# SCH_ONO_R2.net
KiCad netlist of a schematic drawn in EasyEDA
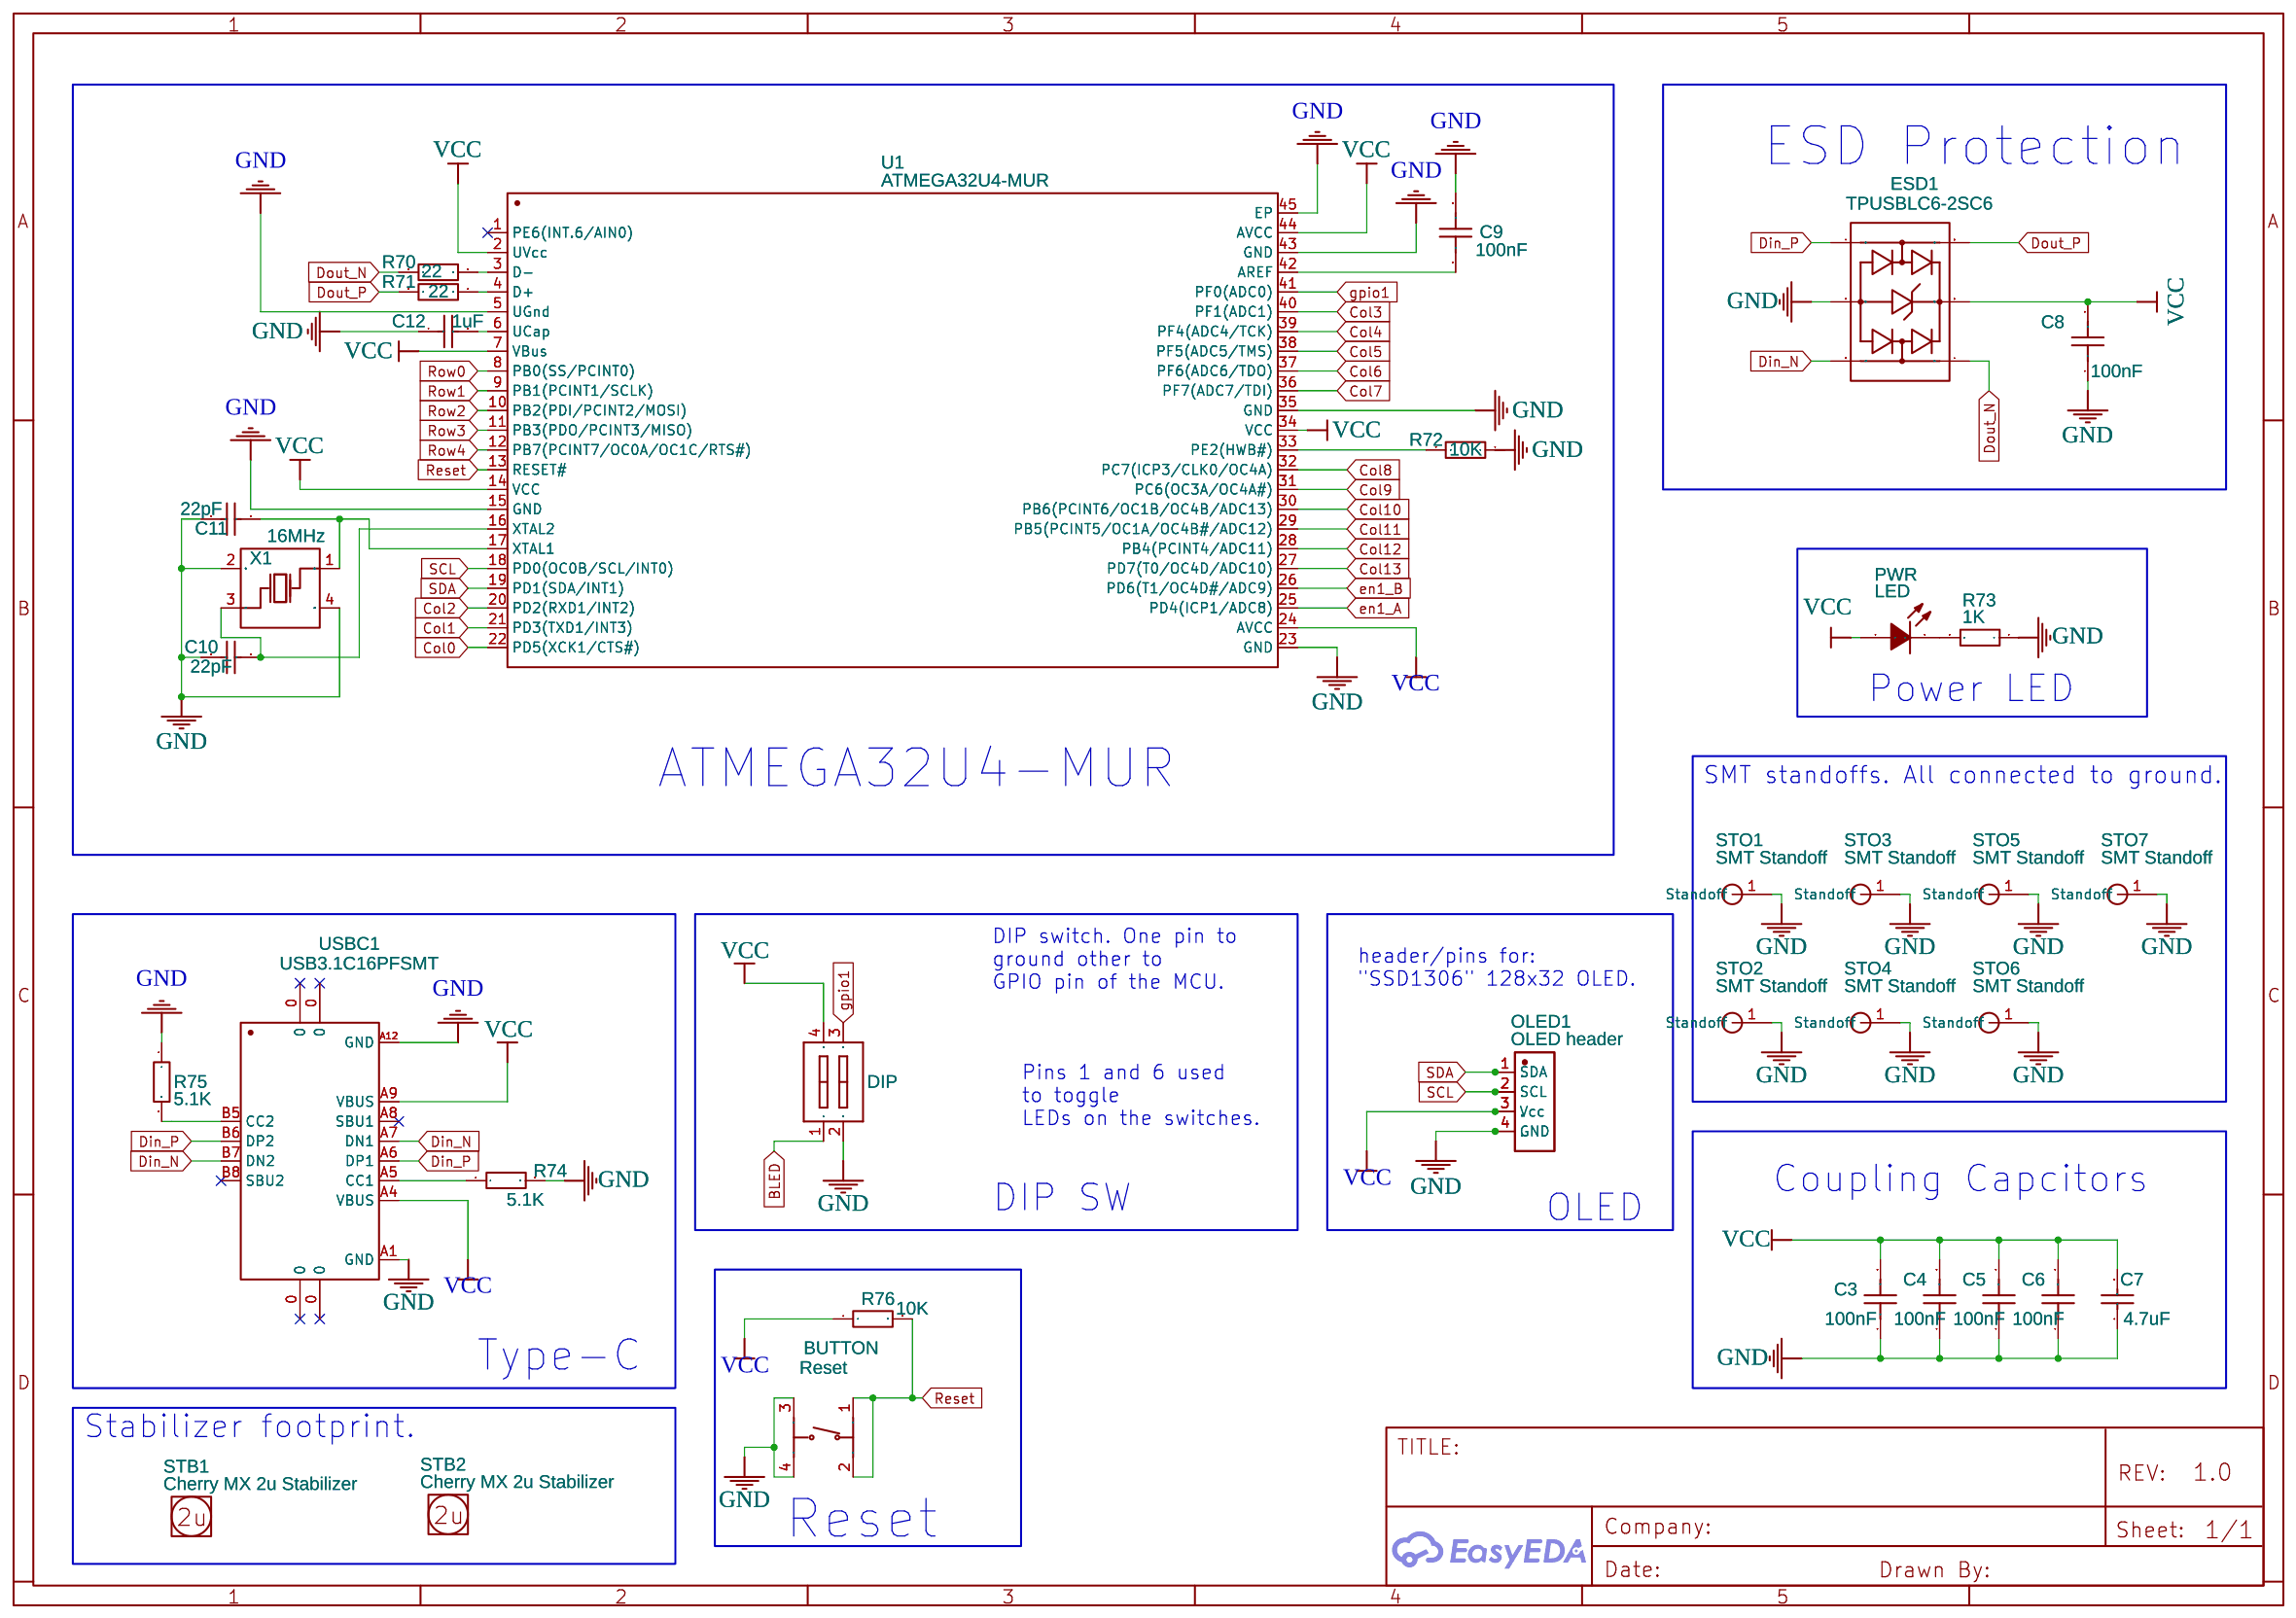
[diagram p0: Atmega MCU copy]
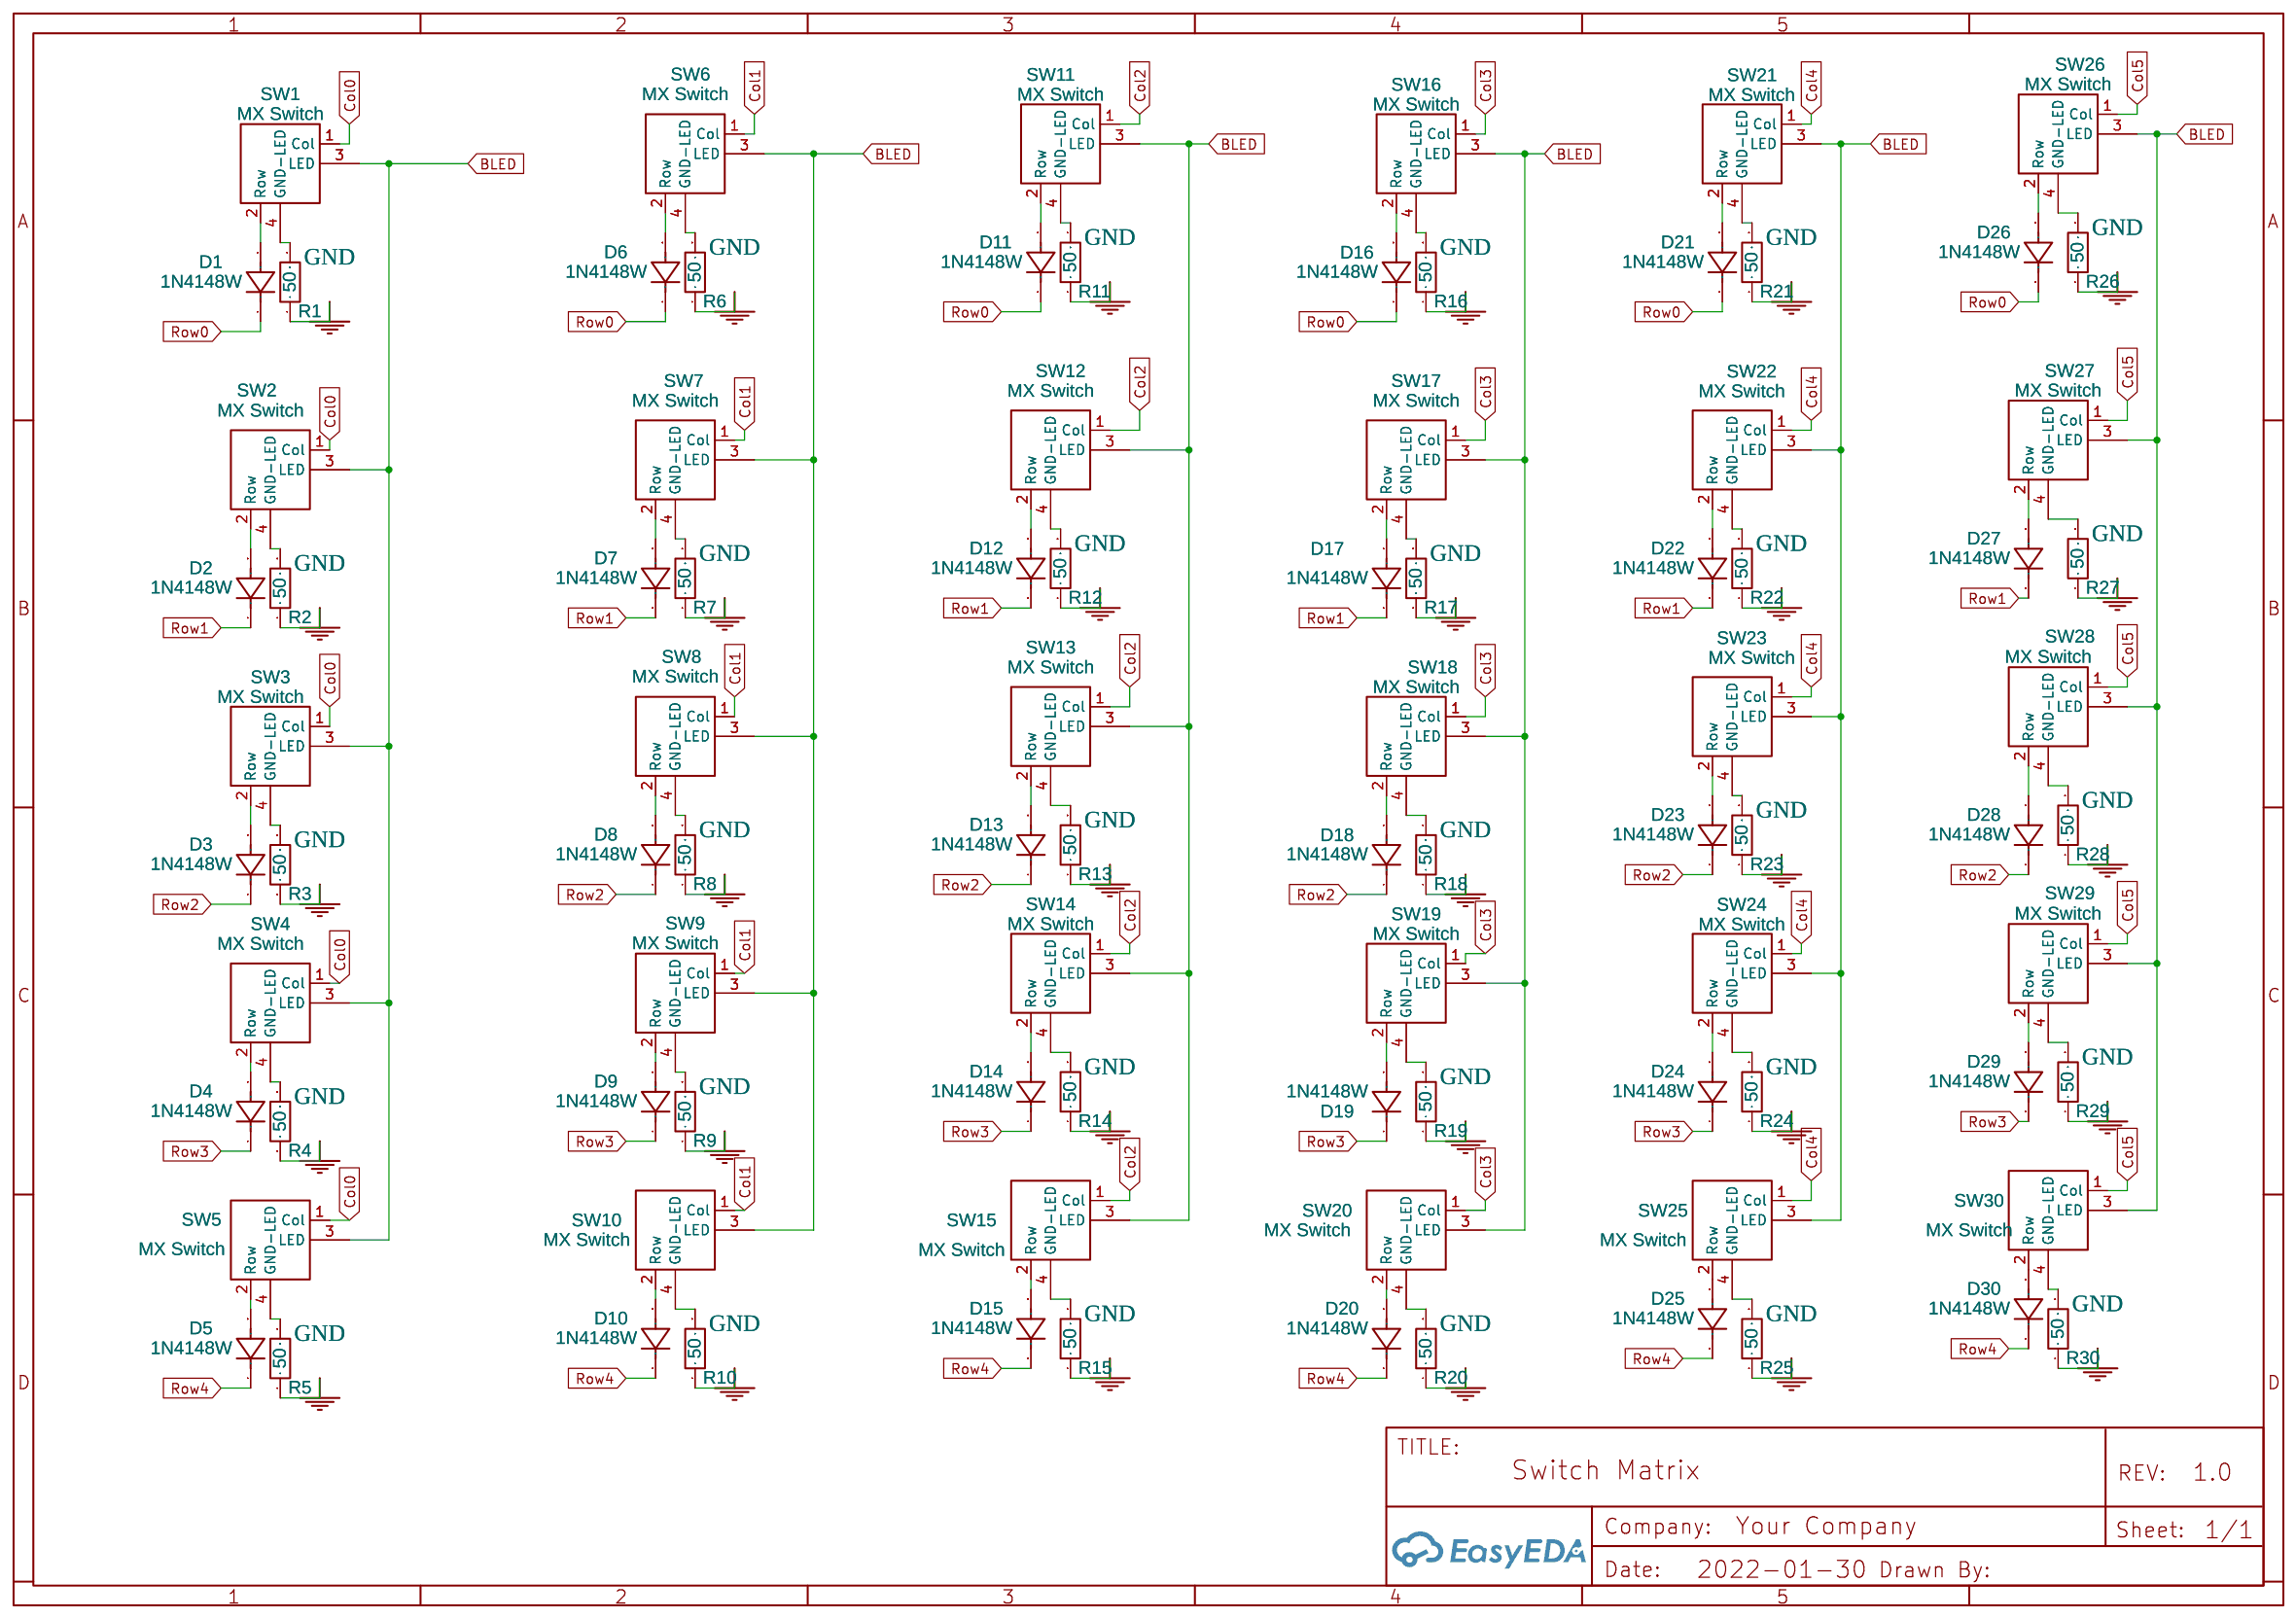
[diagram p1: First 6 Colimn]
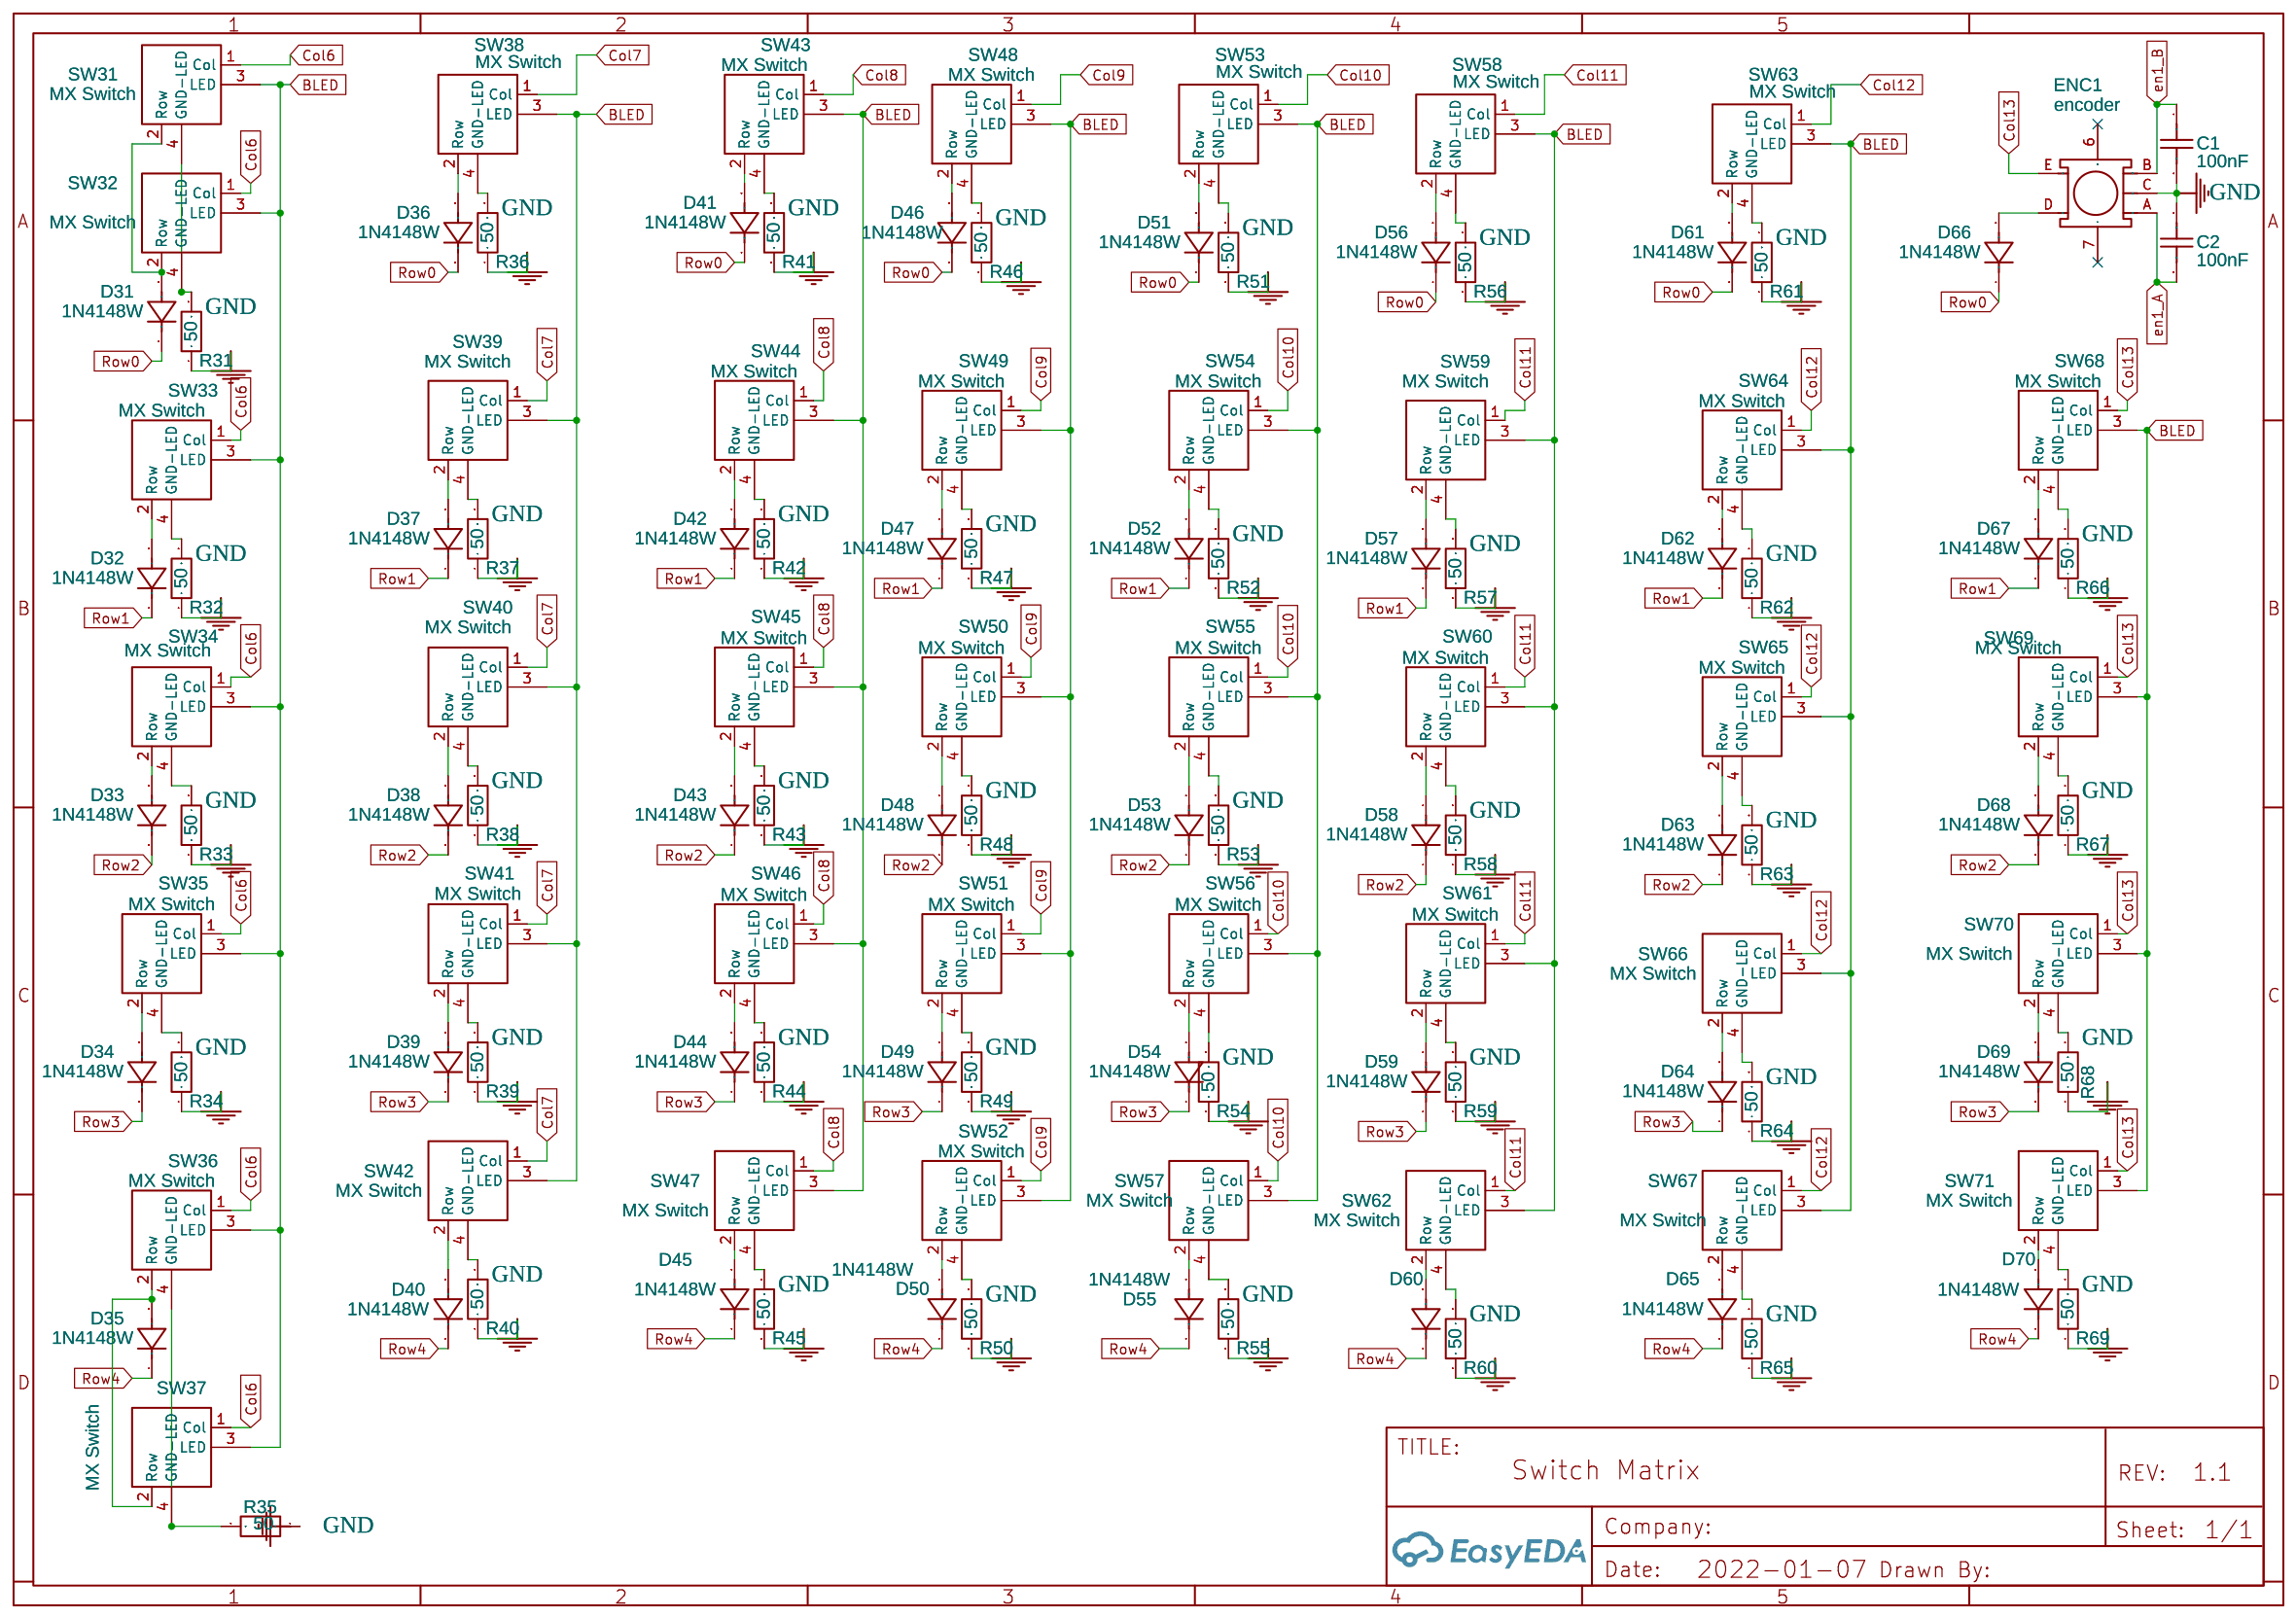
[diagram p2: Last 8 Col]

(export (version "E")
  (design (tool "Eeschema 10.0.6"))
  (components
    (comp (ref "BUTTON")
      (value "Reset")
      (fields
        (field (name "BOM_Manufacturer Part") "TS-1187A-B-A-B")
        (field (name "BOM_Supplier Part") "C318884")
      )
      (libsource (lib "") (part "TS-1187A-B-A-B"))
    )
    (comp (ref "C3")
      (value "100nF")
      (fields
        (field (name "BOM_Manufacturer Part") "CC0603KRX7R9BB104")
        (field (name "BOM_Supplier Part") "C14663")
      )
      (libsource (lib "") (part "CC0603KRX7R9BB104"))
    )
    (comp (ref "C4")
      (value "100nF")
      (fields
        (field (name "BOM_Manufacturer Part") "CC0603KRX7R9BB104")
        (field (name "BOM_Supplier Part") "C14663")
      )
      (libsource (lib "") (part "CC0603KRX7R9BB104"))
    )
    (comp (ref "C5")
      (value "100nF")
      (fields
        (field (name "BOM_Manufacturer Part") "CC0603KRX7R9BB104")
        (field (name "BOM_Supplier Part") "C14663")
      )
      (libsource (lib "") (part "CC0603KRX7R9BB104"))
    )
    (comp (ref "C6")
      (value "100nF")
      (fields
        (field (name "BOM_Manufacturer Part") "CC0603KRX7R9BB104")
        (field (name "BOM_Supplier Part") "C14663")
      )
      (libsource (lib "") (part "CC0603KRX7R9BB104"))
    )
    (comp (ref "C7")
      (value "4.7uF")
      (fields
        (field (name "BOM_Manufacturer Part") "CL10A475KO8NNNC")
        (field (name "BOM_Supplier Part") "C19666")
      )
      (libsource (lib "") (part "CL10A475KO8NNNC"))
    )
    (comp (ref "C8")
      (value "100nF")
      (fields
        (field (name "BOM_Manufacturer Part") "CC0603KRX7R9BB104")
        (field (name "BOM_Supplier Part") "C14663")
      )
      (libsource (lib "") (part "CC0603KRX7R9BB104"))
    )
    (comp (ref "C9")
      (value "100nF")
      (fields
        (field (name "BOM_Manufacturer Part") "CC0603KRX7R9BB104")
        (field (name "BOM_Supplier Part") "C14663")
      )
      (libsource (lib "") (part "CC0603KRX7R9BB104"))
    )
    (comp (ref "C10")
      (value "22pF")
      (fields
        (field (name "BOM_Manufacturer Part") "CL10C220JB8NNNC")
        (field (name "BOM_Supplier Part") "C1653")
      )
      (libsource (lib "") (part "CL10C220JB8NNNC"))
    )
    (comp (ref "C11")
      (value "22pF")
      (fields
        (field (name "BOM_Manufacturer Part") "CL10C220JB8NNNC")
        (field (name "BOM_Supplier Part") "C1653")
      )
      (libsource (lib "") (part "CL10C220JB8NNNC"))
    )
    (comp (ref "C12")
      (value "1uF")
      (fields
        (field (name "BOM_Manufacturer Part") "CL10A105KB8NNNC")
        (field (name "BOM_Supplier Part") "C15849")
      )
      (libsource (lib "") (part "CL10A105KB8NNNC"))
    )
    (comp (ref "DIP")
      (value "DSIC02LS-P_C489174")
      (fields
        (field (name "BOM_Manufacturer Part") "DSIC02LS-P")
        (field (name "BOM_Supplier Part") "C489174")
      )
      (libsource (lib "") (part "DSIC02LS-P_C489174"))
    )
    (comp (ref "ESD1")
      (value "TPUSBLC6-2SC6")
      (fields (field (name "BOM_Supplier Part") "C558442"))
      (libsource (lib "") (part "TPUSBLC6-2SC6"))
    )
    (comp (ref "OLED1")
      (value "OLED header")
      (fields
        (field (name "BOM_Manufacturer Part") "X4611WRS-04I-C40D28")
        (field (name "BOM_Supplier Part") "C917591")
      )
      (libsource (lib "") (part "X4611WRS-04I-C40D28"))
    )
    (comp (ref "PWR")
      (value "LED")
      (fields
        (field (name "BOM_Manufacturer Part") "TJ-S2012SW8TGLC6B-A5")
        (field (name "BOM_Supplier Part") "C192320")
      )
      (libsource (lib "") (part "TJ-S2012SW8TGLC6B-A5"))
    )
    (comp (ref "R70")
      (value "22")
      (fields
        (field (name "BOM_Manufacturer Part") "0603WAF220JT5E")
        (field (name "BOM_Supplier Part") "C23345")
      )
      (libsource (lib "") (part "0603WAF220JT5E"))
    )
    (comp (ref "R71")
      (value "22")
      (fields
        (field (name "BOM_Manufacturer Part") "0603WAF220JT5E")
        (field (name "BOM_Supplier Part") "C23345")
      )
      (libsource (lib "") (part "0603WAF220JT5E"))
    )
    (comp (ref "R72")
      (value "10K")
      (fields
        (field (name "BOM_Manufacturer Part") "0603WAF1002T5E")
        (field (name "BOM_Supplier Part") "C25804")
      )
      (libsource (lib "") (part "0603WAF1002T5E_1"))
    )
    (comp (ref "R73")
      (value "1K")
      (fields
        (field (name "BOM_Manufacturer Part") "TR0603B1KP0525")
        (field (name "BOM_Supplier Part") "C188364")
      )
      (libsource (lib "") (part "TR0603B1KP0525"))
    )
    (comp (ref "R74")
      (value "5.1K")
      (fields
        (field (name "BOM_Manufacturer Part") "RMC06035.1K1%N")
        (field (name "BOM_Supplier Part") "C269716")
      )
      (libsource (lib "") (part "RMC06035.1K1%N_1"))
    )
    (comp (ref "R75")
      (value "5.1K")
      (fields
        (field (name "BOM_Manufacturer Part") "RMC06035.1K1%N")
        (field (name "BOM_Supplier Part") "C269716")
      )
      (libsource (lib "") (part "RMC06035.1K1%N"))
    )
    (comp (ref "R76")
      (value "10K")
      (fields
        (field (name "BOM_Manufacturer Part") "0603WAF1002T5E")
        (field (name "BOM_Supplier Part") "C25804")
      )
      (libsource (lib "") (part "0603WAF1002T5E"))
    )
    (comp (ref "STB1")
      (value "Cherry MX 2u Stabilizer")
      (fields
        (field (name "BOM_Manufacturer Part") "G99-0742")
        (field (name "BOM_Supplier Part") "540-G99-0742")
      )
      (libsource (lib "") (part "Cherry MX 2u Stabilizer"))
    )
    (comp (ref "STB2")
      (value "Cherry MX 2u Stabilizer")
      (fields
        (field (name "BOM_Manufacturer Part") "G99-0742")
        (field (name "BOM_Supplier Part") "540-G99-0742")
      )
      (libsource (lib "") (part "Cherry MX 2u Stabilizer"))
    )
    (comp (ref "STO1")
      (value "SMT Standoff")
      (fields (field (name "BOM_Manufacturer Part") "9774040151R"))
      (libsource (lib "") (part "SMT Standoff"))
    )
    (comp (ref "STO2")
      (value "SMT Standoff")
      (fields (field (name "BOM_Manufacturer Part") "9774040151R"))
      (libsource (lib "") (part "SMT Standoff"))
    )
    (comp (ref "STO3")
      (value "SMT Standoff")
      (fields (field (name "BOM_Manufacturer Part") "9774040151R"))
      (libsource (lib "") (part "SMT Standoff"))
    )
    (comp (ref "STO4")
      (value "SMT Standoff")
      (fields (field (name "BOM_Manufacturer Part") "9774040151R"))
      (libsource (lib "") (part "SMT Standoff"))
    )
    (comp (ref "STO5")
      (value "SMT Standoff")
      (fields (field (name "BOM_Manufacturer Part") "9774040151R"))
      (libsource (lib "") (part "SMT Standoff"))
    )
    (comp (ref "STO6")
      (value "SMT Standoff")
      (fields (field (name "BOM_Manufacturer Part") "9774040151R"))
      (libsource (lib "") (part "SMT Standoff"))
    )
    (comp (ref "STO7")
      (value "SMT Standoff")
      (fields (field (name "BOM_Manufacturer Part") "9774040151R"))
      (libsource (lib "") (part "SMT Standoff"))
    )
    (comp (ref "U1")
      (value "ATMEGA32U4-MUR")
      (fields (field (name "BOM_Supplier Part") "C45874"))
      (libsource (lib "") (part "ATMEGA32U4-MUR"))
    )
    (comp (ref "U2")
      (value "x")
      (fields
        (field (name "BOM_Manufacturer Part") "PZ2.54-1X4P-ZW")
        (field (name "BOM_Supplier Part") "C2837836")
      )
      (libsource (lib "") (part "PZ2.54-1X4P-ZW"))
    )
    (comp (ref "USBC1")
      (value "USB3.1C16PFSMT")
      (fields (field (name "BOM_Supplier Part") "C167321"))
      (libsource (lib "") (part "USB3.1C16PFSMT"))
    )
    (comp (ref "X1")
      (value "16MHz")
      (fields
        (field (name "BOM_Manufacturer Part") "X322516MLB4SI")
        (field (name "BOM_Supplier Part") "C13738")
      )
      (libsource (lib "") (part "X322516MLB4SI"))
    )
    (comp (ref "D1")
      (value "1N4148W")
      (fields (field (name "BOM_Supplier Part") "C2828417"))
      (libsource (lib "") (part "1N4148W_C2828417"))
    )
    (comp (ref "D2")
      (value "1N4148W")
      (fields (field (name "BOM_Supplier Part") "C2828417"))
      (libsource (lib "") (part "1N4148W_C2828417"))
    )
    (comp (ref "D3")
      (value "1N4148W")
      (fields (field (name "BOM_Supplier Part") "C2828417"))
      (libsource (lib "") (part "1N4148W_C2828417"))
    )
    (comp (ref "D4")
      (value "1N4148W")
      (fields (field (name "BOM_Supplier Part") "C2828417"))
      (libsource (lib "") (part "1N4148W_C2828417"))
    )
    (comp (ref "D5")
      (value "1N4148W")
      (fields (field (name "BOM_Supplier Part") "C2828417"))
      (libsource (lib "") (part "1N4148W_C2828417"))
    )
    (comp (ref "D6")
      (value "1N4148W")
      (fields (field (name "BOM_Supplier Part") "C2828417"))
      (libsource (lib "") (part "1N4148W_C2828417"))
    )
    (comp (ref "D7")
      (value "1N4148W")
      (fields (field (name "BOM_Supplier Part") "C2828417"))
      (libsource (lib "") (part "1N4148W_C2828417"))
    )
    (comp (ref "D8")
      (value "1N4148W")
      (fields (field (name "BOM_Supplier Part") "C2828417"))
      (libsource (lib "") (part "1N4148W_C2828417"))
    )
    (comp (ref "D9")
      (value "1N4148W")
      (fields (field (name "BOM_Supplier Part") "C2828417"))
      (libsource (lib "") (part "1N4148W_C2828417"))
    )
    (comp (ref "D10")
      (value "1N4148W")
      (fields (field (name "BOM_Supplier Part") "C2828417"))
      (libsource (lib "") (part "1N4148W_C2828417"))
    )
    (comp (ref "D11")
      (value "1N4148W")
      (fields (field (name "BOM_Supplier Part") "C2828417"))
      (libsource (lib "") (part "1N4148W_C2828417"))
    )
    (comp (ref "D12")
      (value "1N4148W")
      (fields (field (name "BOM_Supplier Part") "C2828417"))
      (libsource (lib "") (part "1N4148W_C2828417"))
    )
    (comp (ref "D13")
      (value "1N4148W")
      (fields (field (name "BOM_Supplier Part") "C2828417"))
      (libsource (lib "") (part "1N4148W_C2828417"))
    )
    (comp (ref "D14")
      (value "1N4148W")
      (fields (field (name "BOM_Supplier Part") "C2828417"))
      (libsource (lib "") (part "1N4148W_C2828417"))
    )
    (comp (ref "D15")
      (value "1N4148W")
      (fields (field (name "BOM_Supplier Part") "C2828417"))
      (libsource (lib "") (part "1N4148W_C2828417"))
    )
    (comp (ref "D16")
      (value "1N4148W")
      (fields (field (name "BOM_Supplier Part") "C2828417"))
      (libsource (lib "") (part "1N4148W_C2828417"))
    )
    (comp (ref "D17")
      (value "1N4148W")
      (fields (field (name "BOM_Supplier Part") "C2828417"))
      (libsource (lib "") (part "1N4148W_C2828417"))
    )
    (comp (ref "D18")
      (value "1N4148W")
      (fields (field (name "BOM_Supplier Part") "C2828417"))
      (libsource (lib "") (part "1N4148W_C2828417"))
    )
    (comp (ref "D19")
      (value "1N4148W")
      (fields (field (name "BOM_Supplier Part") "C2828417"))
      (libsource (lib "") (part "1N4148W_C2828417"))
    )
    (comp (ref "D20")
      (value "1N4148W")
      (fields (field (name "BOM_Supplier Part") "C2828417"))
      (libsource (lib "") (part "1N4148W_C2828417"))
    )
    (comp (ref "D21")
      (value "1N4148W")
      (fields (field (name "BOM_Supplier Part") "C2828417"))
      (libsource (lib "") (part "1N4148W_C2828417"))
    )
    (comp (ref "D22")
      (value "1N4148W")
      (fields (field (name "BOM_Supplier Part") "C2828417"))
      (libsource (lib "") (part "1N4148W_C2828417"))
    )
    (comp (ref "D23")
      (value "1N4148W")
      (fields (field (name "BOM_Supplier Part") "C2828417"))
      (libsource (lib "") (part "1N4148W_C2828417"))
    )
    (comp (ref "D24")
      (value "1N4148W")
      (fields (field (name "BOM_Supplier Part") "C2828417"))
      (libsource (lib "") (part "1N4148W_C2828417"))
    )
    (comp (ref "D25")
      (value "1N4148W")
      (fields (field (name "BOM_Supplier Part") "C2828417"))
      (libsource (lib "") (part "1N4148W_C2828417"))
    )
    (comp (ref "D26")
      (value "1N4148W")
      (fields (field (name "BOM_Supplier Part") "C2828417"))
      (libsource (lib "") (part "1N4148W_C2828417"))
    )
    (comp (ref "D27")
      (value "1N4148W")
      (fields (field (name "BOM_Supplier Part") "C2828417"))
      (libsource (lib "") (part "1N4148W_C2828417"))
    )
    (comp (ref "D28")
      (value "1N4148W")
      (fields (field (name "BOM_Supplier Part") "C2828417"))
      (libsource (lib "") (part "1N4148W_C2828417"))
    )
    (comp (ref "D29")
      (value "1N4148W")
      (fields (field (name "BOM_Supplier Part") "C2828417"))
      (libsource (lib "") (part "1N4148W_C2828417"))
    )
    (comp (ref "D30")
      (value "1N4148W")
      (fields (field (name "BOM_Supplier Part") "C2828417"))
      (libsource (lib "") (part "1N4148W_C2828417"))
    )
    (comp (ref "R1")
      (value "50")
      (fields
        (field (name "BOM_Manufacturer Part") "HP03W5F500JT5E")
        (field (name "BOM_Supplier Part") "C2759402")
      )
      (libsource (lib "") (part "HP03W5F500JT5E"))
    )
    (comp (ref "R2")
      (value "50")
      (fields
        (field (name "BOM_Manufacturer Part") "HP03W5F500JT5E")
        (field (name "BOM_Supplier Part") "C2759402")
      )
      (libsource (lib "") (part "HP03W5F500JT5E"))
    )
    (comp (ref "R3")
      (value "50")
      (fields
        (field (name "BOM_Manufacturer Part") "HP03W5F500JT5E")
        (field (name "BOM_Supplier Part") "C2759402")
      )
      (libsource (lib "") (part "HP03W5F500JT5E"))
    )
    (comp (ref "R4")
      (value "50")
      (fields
        (field (name "BOM_Manufacturer Part") "HP03W5F500JT5E")
        (field (name "BOM_Supplier Part") "C2759402")
      )
      (libsource (lib "") (part "HP03W5F500JT5E"))
    )
    (comp (ref "R5")
      (value "50")
      (fields
        (field (name "BOM_Manufacturer Part") "HP03W5F500JT5E")
        (field (name "BOM_Supplier Part") "C2759402")
      )
      (libsource (lib "") (part "HP03W5F500JT5E"))
    )
    (comp (ref "R6")
      (value "50")
      (fields
        (field (name "BOM_Manufacturer Part") "HP03W5F500JT5E")
        (field (name "BOM_Supplier Part") "C2759402")
      )
      (libsource (lib "") (part "HP03W5F500JT5E"))
    )
    (comp (ref "R7")
      (value "50")
      (fields
        (field (name "BOM_Manufacturer Part") "HP03W5F500JT5E")
        (field (name "BOM_Supplier Part") "C2759402")
      )
      (libsource (lib "") (part "HP03W5F500JT5E"))
    )
    (comp (ref "R8")
      (value "50")
      (fields
        (field (name "BOM_Manufacturer Part") "HP03W5F500JT5E")
        (field (name "BOM_Supplier Part") "C2759402")
      )
      (libsource (lib "") (part "HP03W5F500JT5E"))
    )
    (comp (ref "R9")
      (value "50")
      (fields
        (field (name "BOM_Manufacturer Part") "HP03W5F500JT5E")
        (field (name "BOM_Supplier Part") "C2759402")
      )
      (libsource (lib "") (part "HP03W5F500JT5E"))
    )
    (comp (ref "R10")
      (value "50")
      (fields
        (field (name "BOM_Manufacturer Part") "HP03W5F500JT5E")
        (field (name "BOM_Supplier Part") "C2759402")
      )
      (libsource (lib "") (part "HP03W5F500JT5E"))
    )
    (comp (ref "R11")
      (value "50")
      (fields
        (field (name "BOM_Manufacturer Part") "HP03W5F500JT5E")
        (field (name "BOM_Supplier Part") "C2759402")
      )
      (libsource (lib "") (part "HP03W5F500JT5E"))
    )
    (comp (ref "R12")
      (value "50")
      (fields
        (field (name "BOM_Manufacturer Part") "HP03W5F500JT5E")
        (field (name "BOM_Supplier Part") "C2759402")
      )
      (libsource (lib "") (part "HP03W5F500JT5E"))
    )
    (comp (ref "R13")
      (value "50")
      (fields
        (field (name "BOM_Manufacturer Part") "HP03W5F500JT5E")
        (field (name "BOM_Supplier Part") "C2759402")
      )
      (libsource (lib "") (part "HP03W5F500JT5E"))
    )
    (comp (ref "R14")
      (value "50")
      (fields
        (field (name "BOM_Manufacturer Part") "HP03W5F500JT5E")
        (field (name "BOM_Supplier Part") "C2759402")
      )
      (libsource (lib "") (part "HP03W5F500JT5E"))
    )
    (comp (ref "R15")
      (value "50")
      (fields
        (field (name "BOM_Manufacturer Part") "HP03W5F500JT5E")
        (field (name "BOM_Supplier Part") "C2759402")
      )
      (libsource (lib "") (part "HP03W5F500JT5E"))
    )
    (comp (ref "R16")
      (value "50")
      (fields
        (field (name "BOM_Manufacturer Part") "HP03W5F500JT5E")
        (field (name "BOM_Supplier Part") "C2759402")
      )
      (libsource (lib "") (part "HP03W5F500JT5E"))
    )
    (comp (ref "R17")
      (value "50")
      (fields
        (field (name "BOM_Manufacturer Part") "HP03W5F500JT5E")
        (field (name "BOM_Supplier Part") "C2759402")
      )
      (libsource (lib "") (part "HP03W5F500JT5E"))
    )
    (comp (ref "R18")
      (value "50")
      (fields
        (field (name "BOM_Manufacturer Part") "HP03W5F500JT5E")
        (field (name "BOM_Supplier Part") "C2759402")
      )
      (libsource (lib "") (part "HP03W5F500JT5E"))
    )
    (comp (ref "R19")
      (value "50")
      (fields
        (field (name "BOM_Manufacturer Part") "HP03W5F500JT5E")
        (field (name "BOM_Supplier Part") "C2759402")
      )
      (libsource (lib "") (part "HP03W5F500JT5E"))
    )
    (comp (ref "R20")
      (value "50")
      (fields
        (field (name "BOM_Manufacturer Part") "HP03W5F500JT5E")
        (field (name "BOM_Supplier Part") "C2759402")
      )
      (libsource (lib "") (part "HP03W5F500JT5E"))
    )
    (comp (ref "R21")
      (value "50")
      (fields
        (field (name "BOM_Manufacturer Part") "HP03W5F500JT5E")
        (field (name "BOM_Supplier Part") "C2759402")
      )
      (libsource (lib "") (part "HP03W5F500JT5E"))
    )
    (comp (ref "R22")
      (value "50")
      (fields
        (field (name "BOM_Manufacturer Part") "HP03W5F500JT5E")
        (field (name "BOM_Supplier Part") "C2759402")
      )
      (libsource (lib "") (part "HP03W5F500JT5E"))
    )
    (comp (ref "R23")
      (value "50")
      (fields
        (field (name "BOM_Manufacturer Part") "HP03W5F500JT5E")
        (field (name "BOM_Supplier Part") "C2759402")
      )
      (libsource (lib "") (part "HP03W5F500JT5E"))
    )
    (comp (ref "R24")
      (value "50")
      (fields
        (field (name "BOM_Manufacturer Part") "HP03W5F500JT5E")
        (field (name "BOM_Supplier Part") "C2759402")
      )
      (libsource (lib "") (part "HP03W5F500JT5E"))
    )
    (comp (ref "R25")
      (value "50")
      (fields
        (field (name "BOM_Manufacturer Part") "HP03W5F500JT5E")
        (field (name "BOM_Supplier Part") "C2759402")
      )
      (libsource (lib "") (part "HP03W5F500JT5E"))
    )
    (comp (ref "R26")
      (value "50")
      (fields
        (field (name "BOM_Manufacturer Part") "HP03W5F500JT5E")
        (field (name "BOM_Supplier Part") "C2759402")
      )
      (libsource (lib "") (part "HP03W5F500JT5E"))
    )
    (comp (ref "R27")
      (value "50")
      (fields
        (field (name "BOM_Manufacturer Part") "HP03W5F500JT5E")
        (field (name "BOM_Supplier Part") "C2759402")
      )
      (libsource (lib "") (part "HP03W5F500JT5E"))
    )
    (comp (ref "R28")
      (value "50")
      (fields
        (field (name "BOM_Manufacturer Part") "HP03W5F500JT5E")
        (field (name "BOM_Supplier Part") "C2759402")
      )
      (libsource (lib "") (part "HP03W5F500JT5E"))
    )
    (comp (ref "R29")
      (value "50")
      (fields
        (field (name "BOM_Manufacturer Part") "HP03W5F500JT5E")
        (field (name "BOM_Supplier Part") "C2759402")
      )
      (libsource (lib "") (part "HP03W5F500JT5E"))
    )
    (comp (ref "R30")
      (value "50")
      (fields
        (field (name "BOM_Manufacturer Part") "HP03W5F500JT5E")
        (field (name "BOM_Supplier Part") "C2759402")
      )
      (libsource (lib "") (part "HP03W5F500JT5E"))
    )
    (comp (ref "SW1")
      (value "MX Switch")
      (fields (field (name "BOM_Supplier Part") "Cherry MX or Alps/Matias switch"))
      (libsource (lib "") (part "MX Switch"))
    )
    (comp (ref "SW2")
      (value "MX Switch")
      (fields (field (name "BOM_Supplier Part") "Cherry MX or Alps/Matias switch"))
      (libsource (lib "") (part "MX Switch"))
    )
    (comp (ref "SW3")
      (value "MX Switch")
      (fields (field (name "BOM_Supplier Part") "Cherry MX or Alps/Matias switch"))
      (libsource (lib "") (part "MX Switch"))
    )
    (comp (ref "SW4")
      (value "MX Switch")
      (fields (field (name "BOM_Supplier Part") "Cherry MX or Alps/Matias switch"))
      (libsource (lib "") (part "MX Switch"))
    )
    (comp (ref "SW5")
      (value "MX Switch")
      (fields (field (name "BOM_Supplier Part") "Cherry MX or Alps/Matias switch"))
      (libsource (lib "") (part "MX Switch"))
    )
    (comp (ref "SW6")
      (value "MX Switch")
      (fields (field (name "BOM_Supplier Part") "Cherry MX or Alps/Matias switch"))
      (libsource (lib "") (part "MX Switch"))
    )
    (comp (ref "SW7")
      (value "MX Switch")
      (fields (field (name "BOM_Supplier Part") "Cherry MX or Alps/Matias switch"))
      (libsource (lib "") (part "MX Switch"))
    )
    (comp (ref "SW8")
      (value "MX Switch")
      (fields (field (name "BOM_Supplier Part") "Cherry MX or Alps/Matias switch"))
      (libsource (lib "") (part "MX Switch"))
    )
    (comp (ref "SW9")
      (value "MX Switch")
      (fields (field (name "BOM_Supplier Part") "Cherry MX or Alps/Matias switch"))
      (libsource (lib "") (part "MX Switch"))
    )
    (comp (ref "SW10")
      (value "MX Switch")
      (fields (field (name "BOM_Supplier Part") "Cherry MX or Alps/Matias switch"))
      (libsource (lib "") (part "MX Switch"))
    )
    (comp (ref "SW11")
      (value "MX Switch")
      (fields (field (name "BOM_Supplier Part") "Cherry MX or Alps/Matias switch"))
      (libsource (lib "") (part "MX Switch"))
    )
    (comp (ref "SW12")
      (value "MX Switch")
      (fields (field (name "BOM_Supplier Part") "Cherry MX or Alps/Matias switch"))
      (libsource (lib "") (part "MX Switch"))
    )
    (comp (ref "SW13")
      (value "MX Switch")
      (fields (field (name "BOM_Supplier Part") "Cherry MX or Alps/Matias switch"))
      (libsource (lib "") (part "MX Switch"))
    )
    (comp (ref "SW14")
      (value "MX Switch")
      (fields (field (name "BOM_Supplier Part") "Cherry MX or Alps/Matias switch"))
      (libsource (lib "") (part "MX Switch"))
    )
    (comp (ref "SW15")
      (value "MX Switch")
      (fields (field (name "BOM_Supplier Part") "Cherry MX or Alps/Matias switch"))
      (libsource (lib "") (part "MX Switch"))
    )
    (comp (ref "SW16")
      (value "MX Switch")
      (fields (field (name "BOM_Supplier Part") "Cherry MX or Alps/Matias switch"))
      (libsource (lib "") (part "MX Switch"))
    )
    (comp (ref "SW17")
      (value "MX Switch")
      (fields (field (name "BOM_Supplier Part") "Cherry MX or Alps/Matias switch"))
      (libsource (lib "") (part "MX Switch"))
    )
    (comp (ref "SW18")
      (value "MX Switch")
      (fields (field (name "BOM_Supplier Part") "Cherry MX or Alps/Matias switch"))
      (libsource (lib "") (part "MX Switch"))
    )
    (comp (ref "SW19")
      (value "MX Switch")
      (fields (field (name "BOM_Supplier Part") "Cherry MX or Alps/Matias switch"))
      (libsource (lib "") (part "MX Switch"))
    )
    (comp (ref "SW20")
      (value "MX Switch")
      (fields (field (name "BOM_Supplier Part") "Cherry MX or Alps/Matias switch"))
      (libsource (lib "") (part "MX Switch"))
    )
    (comp (ref "SW21")
      (value "MX Switch")
      (fields (field (name "BOM_Supplier Part") "Cherry MX or Alps/Matias switch"))
      (libsource (lib "") (part "MX Switch"))
    )
    (comp (ref "SW22")
      (value "MX Switch")
      (fields (field (name "BOM_Supplier Part") "Cherry MX or Alps/Matias switch"))
      (libsource (lib "") (part "MX Switch"))
    )
    (comp (ref "SW23")
      (value "MX Switch")
      (fields (field (name "BOM_Supplier Part") "Cherry MX or Alps/Matias switch"))
      (libsource (lib "") (part "MX Switch"))
    )
    (comp (ref "SW24")
      (value "MX Switch")
      (fields (field (name "BOM_Supplier Part") "Cherry MX or Alps/Matias switch"))
      (libsource (lib "") (part "MX Switch"))
    )
    (comp (ref "SW25")
      (value "MX Switch")
      (fields (field (name "BOM_Supplier Part") "Cherry MX or Alps/Matias switch"))
      (libsource (lib "") (part "MX Switch"))
    )
    (comp (ref "SW26")
      (value "MX Switch")
      (fields (field (name "BOM_Supplier Part") "Cherry MX or Alps/Matias switch"))
      (libsource (lib "") (part "MX Switch"))
    )
    (comp (ref "SW27")
      (value "MX Switch")
      (fields (field (name "BOM_Supplier Part") "Cherry MX or Alps/Matias switch"))
      (libsource (lib "") (part "MX Switch"))
    )
    (comp (ref "SW28")
      (value "MX Switch")
      (fields (field (name "BOM_Supplier Part") "Cherry MX or Alps/Matias switch"))
      (libsource (lib "") (part "MX Switch"))
    )
    (comp (ref "SW29")
      (value "MX Switch")
      (fields (field (name "BOM_Supplier Part") "Cherry MX or Alps/Matias switch"))
      (libsource (lib "") (part "MX Switch"))
    )
    (comp (ref "SW30")
      (value "MX Switch")
      (fields (field (name "BOM_Supplier Part") "Cherry MX or Alps/Matias switch"))
      (libsource (lib "") (part "MX Switch"))
    )
    (comp (ref "C1")
      (value "100nF")
      (fields
        (field (name "BOM_Manufacturer Part") "CC0603KRX7R9BB104")
        (field (name "BOM_Supplier Part") "C14663")
      )
      (libsource (lib "") (part "CC0603KRX7R9BB104"))
    )
    (comp (ref "C2")
      (value "100nF")
      (fields
        (field (name "BOM_Manufacturer Part") "CC0603KRX7R9BB104")
        (field (name "BOM_Supplier Part") "C14663")
      )
      (libsource (lib "") (part "CC0603KRX7R9BB104"))
    )
    (comp (ref "D31")
      (value "1N4148W")
      (fields (field (name "BOM_Supplier Part") "C2828417"))
      (libsource (lib "") (part "1N4148W_C2828417"))
    )
    (comp (ref "D32")
      (value "1N4148W")
      (fields (field (name "BOM_Supplier Part") "C2828417"))
      (libsource (lib "") (part "1N4148W_C2828417"))
    )
    (comp (ref "D33")
      (value "1N4148W")
      (fields (field (name "BOM_Supplier Part") "C2828417"))
      (libsource (lib "") (part "1N4148W_C2828417"))
    )
    (comp (ref "D34")
      (value "1N4148W")
      (fields (field (name "BOM_Supplier Part") "C2828417"))
      (libsource (lib "") (part "1N4148W_C2828417"))
    )
    (comp (ref "D35")
      (value "1N4148W")
      (fields (field (name "BOM_Supplier Part") "C2828417"))
      (libsource (lib "") (part "1N4148W_C2828417"))
    )
    (comp (ref "D36")
      (value "1N4148W")
      (fields (field (name "BOM_Supplier Part") "C2828417"))
      (libsource (lib "") (part "1N4148W_C2828417"))
    )
    (comp (ref "D37")
      (value "1N4148W")
      (fields (field (name "BOM_Supplier Part") "C2828417"))
      (libsource (lib "") (part "1N4148W_C2828417"))
    )
    (comp (ref "D38")
      (value "1N4148W")
      (fields (field (name "BOM_Supplier Part") "C2828417"))
      (libsource (lib "") (part "1N4148W_C2828417"))
    )
    (comp (ref "D39")
      (value "1N4148W")
      (fields (field (name "BOM_Supplier Part") "C2828417"))
      (libsource (lib "") (part "1N4148W_C2828417"))
    )
    (comp (ref "D40")
      (value "1N4148W")
      (fields (field (name "BOM_Supplier Part") "C2828417"))
      (libsource (lib "") (part "1N4148W_C2828417"))
    )
    (comp (ref "D41")
      (value "1N4148W")
      (fields (field (name "BOM_Supplier Part") "C2828417"))
      (libsource (lib "") (part "1N4148W_C2828417"))
    )
    (comp (ref "D42")
      (value "1N4148W")
      (fields (field (name "BOM_Supplier Part") "C2828417"))
      (libsource (lib "") (part "1N4148W_C2828417"))
    )
    (comp (ref "D43")
      (value "1N4148W")
      (fields (field (name "BOM_Supplier Part") "C2828417"))
      (libsource (lib "") (part "1N4148W_C2828417"))
    )
    (comp (ref "D44")
      (value "1N4148W")
      (fields (field (name "BOM_Supplier Part") "C2828417"))
      (libsource (lib "") (part "1N4148W_C2828417"))
    )
    (comp (ref "D45")
      (value "1N4148W")
      (fields (field (name "BOM_Supplier Part") "C2828417"))
      (libsource (lib "") (part "1N4148W_C2828417"))
    )
    (comp (ref "D46")
      (value "1N4148W")
      (fields (field (name "BOM_Supplier Part") "C2828417"))
      (libsource (lib "") (part "1N4148W_C2828417"))
    )
    (comp (ref "D47")
      (value "1N4148W")
      (fields (field (name "BOM_Supplier Part") "C2828417"))
      (libsource (lib "") (part "1N4148W_C2828417"))
    )
    (comp (ref "D48")
      (value "1N4148W")
      (fields (field (name "BOM_Supplier Part") "C2828417"))
      (libsource (lib "") (part "1N4148W_C2828417"))
    )
    (comp (ref "D49")
      (value "1N4148W")
      (fields (field (name "BOM_Supplier Part") "C2828417"))
      (libsource (lib "") (part "1N4148W_C2828417"))
    )
    (comp (ref "D50")
      (value "1N4148W")
      (fields (field (name "BOM_Supplier Part") "C2828417"))
      (libsource (lib "") (part "1N4148W_C2828417"))
    )
    (comp (ref "D51")
      (value "1N4148W")
      (fields (field (name "BOM_Supplier Part") "C2828417"))
      (libsource (lib "") (part "1N4148W_C2828417"))
    )
    (comp (ref "D52")
      (value "1N4148W")
      (fields (field (name "BOM_Supplier Part") "C2828417"))
      (libsource (lib "") (part "1N4148W_C2828417"))
    )
    (comp (ref "D53")
      (value "1N4148W")
      (fields (field (name "BOM_Supplier Part") "C2828417"))
      (libsource (lib "") (part "1N4148W_C2828417"))
    )
    (comp (ref "D54")
      (value "1N4148W")
      (fields (field (name "BOM_Supplier Part") "C2828417"))
      (libsource (lib "") (part "1N4148W_C2828417"))
    )
    (comp (ref "D55")
      (value "1N4148W")
      (fields (field (name "BOM_Supplier Part") "C2828417"))
      (libsource (lib "") (part "1N4148W_C2828417"))
    )
    (comp (ref "D56")
      (value "1N4148W")
      (fields (field (name "BOM_Supplier Part") "C2828417"))
      (libsource (lib "") (part "1N4148W_C2828417"))
    )
    (comp (ref "D57")
      (value "1N4148W")
      (fields (field (name "BOM_Supplier Part") "C2828417"))
      (libsource (lib "") (part "1N4148W_C2828417"))
    )
    (comp (ref "D58")
      (value "1N4148W")
      (fields (field (name "BOM_Supplier Part") "C2828417"))
      (libsource (lib "") (part "1N4148W_C2828417"))
    )
    (comp (ref "D59")
      (value "1N4148W")
      (fields (field (name "BOM_Supplier Part") "C2828417"))
      (libsource (lib "") (part "1N4148W_C2828417"))
    )
    (comp (ref "D60")
      (value "1N4148W")
      (fields (field (name "BOM_Supplier Part") "C2828417"))
      (libsource (lib "") (part "1N4148W_C2828417"))
    )
    (comp (ref "D61")
      (value "1N4148W")
      (fields (field (name "BOM_Supplier Part") "C2828417"))
      (libsource (lib "") (part "1N4148W_C2828417"))
    )
    (comp (ref "D62")
      (value "1N4148W")
      (fields (field (name "BOM_Supplier Part") "C2828417"))
      (libsource (lib "") (part "1N4148W_C2828417"))
    )
    (comp (ref "D63")
      (value "1N4148W")
      (fields (field (name "BOM_Supplier Part") "C2828417"))
      (libsource (lib "") (part "1N4148W_C2828417"))
    )
    (comp (ref "D64")
      (value "1N4148W")
      (fields (field (name "BOM_Supplier Part") "C2828417"))
      (libsource (lib "") (part "1N4148W_C2828417"))
    )
    (comp (ref "D65")
      (value "1N4148W")
      (fields (field (name "BOM_Supplier Part") "C2828417"))
      (libsource (lib "") (part "1N4148W_C2828417"))
    )
    (comp (ref "D66")
      (value "1N4148W")
      (fields (field (name "BOM_Supplier Part") "C2828417"))
      (libsource (lib "") (part "1N4148W_C2828417"))
    )
    (comp (ref "D67")
      (value "1N4148W")
      (fields (field (name "BOM_Supplier Part") "C2828417"))
      (libsource (lib "") (part "1N4148W_C2828417"))
    )
    (comp (ref "D68")
      (value "1N4148W")
      (fields (field (name "BOM_Supplier Part") "C2828417"))
      (libsource (lib "") (part "1N4148W_C2828417"))
    )
    (comp (ref "D69")
      (value "1N4148W")
      (fields (field (name "BOM_Supplier Part") "C2828417"))
      (libsource (lib "") (part "1N4148W_C2828417"))
    )
    (comp (ref "D70")
      (value "1N4148W")
      (fields (field (name "BOM_Supplier Part") "C2828417"))
      (libsource (lib "") (part "1N4148W_C2828417"))
    )
    (comp (ref "ENC1")
      (value "encoder")
      (fields
        (field (name "BOM_Manufacturer Part") "EC11E18244AU")
        (field (name "BOM_Supplier Part") "C202365")
      )
      (libsource (lib "") (part "EC11E18244AU"))
    )
    (comp (ref "R31")
      (value "50")
      (fields
        (field (name "BOM_Manufacturer Part") "HP03W5F500JT5E")
        (field (name "BOM_Supplier Part") "C2759402")
      )
      (libsource (lib "") (part "HP03W5F500JT5E"))
    )
    (comp (ref "R32")
      (value "50")
      (fields
        (field (name "BOM_Manufacturer Part") "HP03W5F500JT5E")
        (field (name "BOM_Supplier Part") "C2759402")
      )
      (libsource (lib "") (part "HP03W5F500JT5E"))
    )
    (comp (ref "R33")
      (value "50")
      (fields
        (field (name "BOM_Manufacturer Part") "HP03W5F500JT5E")
        (field (name "BOM_Supplier Part") "C2759402")
      )
      (libsource (lib "") (part "HP03W5F500JT5E"))
    )
    (comp (ref "R34")
      (value "50")
      (fields
        (field (name "BOM_Manufacturer Part") "HP03W5F500JT5E")
        (field (name "BOM_Supplier Part") "C2759402")
      )
      (libsource (lib "") (part "HP03W5F500JT5E"))
    )
    (comp (ref "R35")
      (value "50")
      (fields
        (field (name "BOM_Manufacturer Part") "HP03W5F500JT5E")
        (field (name "BOM_Supplier Part") "C2759402")
      )
      (libsource (lib "") (part "HP03W5F500JT5E_1"))
    )
    (comp (ref "R36")
      (value "50")
      (fields
        (field (name "BOM_Manufacturer Part") "HP03W5F500JT5E")
        (field (name "BOM_Supplier Part") "C2759402")
      )
      (libsource (lib "") (part "HP03W5F500JT5E"))
    )
    (comp (ref "R37")
      (value "50")
      (fields
        (field (name "BOM_Manufacturer Part") "HP03W5F500JT5E")
        (field (name "BOM_Supplier Part") "C2759402")
      )
      (libsource (lib "") (part "HP03W5F500JT5E"))
    )
    (comp (ref "R38")
      (value "50")
      (fields
        (field (name "BOM_Manufacturer Part") "HP03W5F500JT5E")
        (field (name "BOM_Supplier Part") "C2759402")
      )
      (libsource (lib "") (part "HP03W5F500JT5E"))
    )
    (comp (ref "R39")
      (value "50")
      (fields
        (field (name "BOM_Manufacturer Part") "HP03W5F500JT5E")
        (field (name "BOM_Supplier Part") "C2759402")
      )
      (libsource (lib "") (part "HP03W5F500JT5E"))
    )
    (comp (ref "R40")
      (value "50")
      (fields
        (field (name "BOM_Manufacturer Part") "HP03W5F500JT5E")
        (field (name "BOM_Supplier Part") "C2759402")
      )
      (libsource (lib "") (part "HP03W5F500JT5E"))
    )
    (comp (ref "R41")
      (value "50")
      (fields
        (field (name "BOM_Manufacturer Part") "HP03W5F500JT5E")
        (field (name "BOM_Supplier Part") "C2759402")
      )
      (libsource (lib "") (part "HP03W5F500JT5E"))
    )
    (comp (ref "R42")
      (value "50")
      (fields
        (field (name "BOM_Manufacturer Part") "HP03W5F500JT5E")
        (field (name "BOM_Supplier Part") "C2759402")
      )
      (libsource (lib "") (part "HP03W5F500JT5E"))
    )
    (comp (ref "R43")
      (value "50")
      (fields
        (field (name "BOM_Manufacturer Part") "HP03W5F500JT5E")
        (field (name "BOM_Supplier Part") "C2759402")
      )
      (libsource (lib "") (part "HP03W5F500JT5E"))
    )
    (comp (ref "R44")
      (value "50")
      (fields
        (field (name "BOM_Manufacturer Part") "HP03W5F500JT5E")
        (field (name "BOM_Supplier Part") "C2759402")
      )
      (libsource (lib "") (part "HP03W5F500JT5E"))
    )
    (comp (ref "R45")
      (value "50")
      (fields
        (field (name "BOM_Manufacturer Part") "HP03W5F500JT5E")
        (field (name "BOM_Supplier Part") "C2759402")
      )
      (libsource (lib "") (part "HP03W5F500JT5E"))
    )
    (comp (ref "R46")
      (value "50")
      (fields
        (field (name "BOM_Manufacturer Part") "HP03W5F500JT5E")
        (field (name "BOM_Supplier Part") "C2759402")
      )
      (libsource (lib "") (part "HP03W5F500JT5E"))
    )
    (comp (ref "R47")
      (value "50")
      (fields
        (field (name "BOM_Manufacturer Part") "HP03W5F500JT5E")
        (field (name "BOM_Supplier Part") "C2759402")
      )
      (libsource (lib "") (part "HP03W5F500JT5E"))
    )
    (comp (ref "R48")
      (value "50")
      (fields
        (field (name "BOM_Manufacturer Part") "HP03W5F500JT5E")
        (field (name "BOM_Supplier Part") "C2759402")
      )
      (libsource (lib "") (part "HP03W5F500JT5E"))
    )
    (comp (ref "R49")
      (value "50")
      (fields
        (field (name "BOM_Manufacturer Part") "HP03W5F500JT5E")
        (field (name "BOM_Supplier Part") "C2759402")
      )
      (libsource (lib "") (part "HP03W5F500JT5E"))
    )
    (comp (ref "R50")
      (value "50")
      (fields
        (field (name "BOM_Manufacturer Part") "HP03W5F500JT5E")
        (field (name "BOM_Supplier Part") "C2759402")
      )
      (libsource (lib "") (part "HP03W5F500JT5E"))
    )
    (comp (ref "R51")
      (value "50")
      (fields
        (field (name "BOM_Manufacturer Part") "HP03W5F500JT5E")
        (field (name "BOM_Supplier Part") "C2759402")
      )
      (libsource (lib "") (part "HP03W5F500JT5E"))
    )
    (comp (ref "R52")
      (value "50")
      (fields
        (field (name "BOM_Manufacturer Part") "HP03W5F500JT5E")
        (field (name "BOM_Supplier Part") "C2759402")
      )
      (libsource (lib "") (part "HP03W5F500JT5E"))
    )
    (comp (ref "R53")
      (value "50")
      (fields
        (field (name "BOM_Manufacturer Part") "HP03W5F500JT5E")
        (field (name "BOM_Supplier Part") "C2759402")
      )
      (libsource (lib "") (part "HP03W5F500JT5E"))
    )
    (comp (ref "R54")
      (value "50")
      (fields
        (field (name "BOM_Manufacturer Part") "HP03W5F500JT5E")
        (field (name "BOM_Supplier Part") "C2759402")
      )
      (libsource (lib "") (part "HP03W5F500JT5E"))
    )
    (comp (ref "R55")
      (value "50")
      (fields
        (field (name "BOM_Manufacturer Part") "HP03W5F500JT5E")
        (field (name "BOM_Supplier Part") "C2759402")
      )
      (libsource (lib "") (part "HP03W5F500JT5E"))
    )
    (comp (ref "R56")
      (value "50")
      (fields
        (field (name "BOM_Manufacturer Part") "HP03W5F500JT5E")
        (field (name "BOM_Supplier Part") "C2759402")
      )
      (libsource (lib "") (part "HP03W5F500JT5E"))
    )
    (comp (ref "R57")
      (value "50")
      (fields
        (field (name "BOM_Manufacturer Part") "HP03W5F500JT5E")
        (field (name "BOM_Supplier Part") "C2759402")
      )
      (libsource (lib "") (part "HP03W5F500JT5E"))
    )
    (comp (ref "R58")
      (value "50")
      (fields
        (field (name "BOM_Manufacturer Part") "HP03W5F500JT5E")
        (field (name "BOM_Supplier Part") "C2759402")
      )
      (libsource (lib "") (part "HP03W5F500JT5E"))
    )
    (comp (ref "R59")
      (value "50")
      (fields
        (field (name "BOM_Manufacturer Part") "HP03W5F500JT5E")
        (field (name "BOM_Supplier Part") "C2759402")
      )
      (libsource (lib "") (part "HP03W5F500JT5E"))
    )
    (comp (ref "R60")
      (value "50")
      (fields
        (field (name "BOM_Manufacturer Part") "HP03W5F500JT5E")
        (field (name "BOM_Supplier Part") "C2759402")
      )
      (libsource (lib "") (part "HP03W5F500JT5E"))
    )
    (comp (ref "R61")
      (value "50")
      (fields
        (field (name "BOM_Manufacturer Part") "HP03W5F500JT5E")
        (field (name "BOM_Supplier Part") "C2759402")
      )
      (libsource (lib "") (part "HP03W5F500JT5E"))
    )
    (comp (ref "R62")
      (value "50")
      (fields
        (field (name "BOM_Manufacturer Part") "HP03W5F500JT5E")
        (field (name "BOM_Supplier Part") "C2759402")
      )
      (libsource (lib "") (part "HP03W5F500JT5E"))
    )
    (comp (ref "R63")
      (value "50")
      (fields
        (field (name "BOM_Manufacturer Part") "HP03W5F500JT5E")
        (field (name "BOM_Supplier Part") "C2759402")
      )
      (libsource (lib "") (part "HP03W5F500JT5E"))
    )
    (comp (ref "R64")
      (value "50")
      (fields
        (field (name "BOM_Manufacturer Part") "HP03W5F500JT5E")
        (field (name "BOM_Supplier Part") "C2759402")
      )
      (libsource (lib "") (part "HP03W5F500JT5E"))
    )
    (comp (ref "R65")
      (value "50")
      (fields
        (field (name "BOM_Manufacturer Part") "HP03W5F500JT5E")
        (field (name "BOM_Supplier Part") "C2759402")
      )
      (libsource (lib "") (part "HP03W5F500JT5E"))
    )
    (comp (ref "R66")
      (value "50")
      (fields
        (field (name "BOM_Manufacturer Part") "HP03W5F500JT5E")
        (field (name "BOM_Supplier Part") "C2759402")
      )
      (libsource (lib "") (part "HP03W5F500JT5E"))
    )
    (comp (ref "R67")
      (value "50")
      (fields
        (field (name "BOM_Manufacturer Part") "HP03W5F500JT5E")
        (field (name "BOM_Supplier Part") "C2759402")
      )
      (libsource (lib "") (part "HP03W5F500JT5E"))
    )
    (comp (ref "R68")
      (value "50")
      (fields
        (field (name "BOM_Manufacturer Part") "HP03W5F500JT5E")
        (field (name "BOM_Supplier Part") "C2759402")
      )
      (libsource (lib "") (part "HP03W5F500JT5E"))
    )
    (comp (ref "R69")
      (value "50")
      (fields
        (field (name "BOM_Manufacturer Part") "HP03W5F500JT5E")
        (field (name "BOM_Supplier Part") "C2759402")
      )
      (libsource (lib "") (part "HP03W5F500JT5E"))
    )
    (comp (ref "SW31")
      (value "MX Switch")
      (fields (field (name "BOM_Supplier Part") "Cherry MX or Alps/Matias switch"))
      (libsource (lib "") (part "MX Switch"))
    )
    (comp (ref "SW32")
      (value "MX Switch")
      (fields (field (name "BOM_Supplier Part") "Cherry MX or Alps/Matias switch"))
      (libsource (lib "") (part "MX Switch"))
    )
    (comp (ref "SW33")
      (value "MX Switch")
      (fields (field (name "BOM_Supplier Part") "Cherry MX or Alps/Matias switch"))
      (libsource (lib "") (part "MX Switch"))
    )
    (comp (ref "SW34")
      (value "MX Switch")
      (fields (field (name "BOM_Supplier Part") "Cherry MX or Alps/Matias switch"))
      (libsource (lib "") (part "MX Switch"))
    )
    (comp (ref "SW35")
      (value "MX Switch")
      (fields (field (name "BOM_Supplier Part") "Cherry MX or Alps/Matias switch"))
      (libsource (lib "") (part "MX Switch"))
    )
    (comp (ref "SW36")
      (value "MX Switch")
      (fields (field (name "BOM_Supplier Part") "Cherry MX or Alps/Matias switch"))
      (libsource (lib "") (part "MX Switch"))
    )
    (comp (ref "SW37")
      (value "MX Switch")
      (fields (field (name "BOM_Supplier Part") "Cherry MX or Alps/Matias switch"))
      (libsource (lib "") (part "MX Switch"))
    )
    (comp (ref "SW38")
      (value "MX Switch")
      (fields (field (name "BOM_Supplier Part") "Cherry MX or Alps/Matias switch"))
      (libsource (lib "") (part "MX Switch"))
    )
    (comp (ref "SW39")
      (value "MX Switch")
      (fields (field (name "BOM_Supplier Part") "Cherry MX or Alps/Matias switch"))
      (libsource (lib "") (part "MX Switch"))
    )
    (comp (ref "SW40")
      (value "MX Switch")
      (fields (field (name "BOM_Supplier Part") "Cherry MX or Alps/Matias switch"))
      (libsource (lib "") (part "MX Switch"))
    )
    (comp (ref "SW41")
      (value "MX Switch")
      (fields (field (name "BOM_Supplier Part") "Cherry MX or Alps/Matias switch"))
      (libsource (lib "") (part "MX Switch"))
    )
    (comp (ref "SW42")
      (value "MX Switch")
      (fields (field (name "BOM_Supplier Part") "Cherry MX or Alps/Matias switch"))
      (libsource (lib "") (part "MX Switch"))
    )
    (comp (ref "SW43")
      (value "MX Switch")
      (fields (field (name "BOM_Supplier Part") "Cherry MX or Alps/Matias switch"))
      (libsource (lib "") (part "MX Switch"))
    )
    (comp (ref "SW44")
      (value "MX Switch")
      (fields (field (name "BOM_Supplier Part") "Cherry MX or Alps/Matias switch"))
      (libsource (lib "") (part "MX Switch"))
    )
    (comp (ref "SW45")
      (value "MX Switch")
      (fields (field (name "BOM_Supplier Part") "Cherry MX or Alps/Matias switch"))
      (libsource (lib "") (part "MX Switch"))
    )
    (comp (ref "SW46")
      (value "MX Switch")
      (fields (field (name "BOM_Supplier Part") "Cherry MX or Alps/Matias switch"))
      (libsource (lib "") (part "MX Switch"))
    )
    (comp (ref "SW47")
      (value "MX Switch")
      (fields (field (name "BOM_Supplier Part") "Cherry MX or Alps/Matias switch"))
      (libsource (lib "") (part "MX Switch"))
    )
    (comp (ref "SW48")
      (value "MX Switch")
      (fields (field (name "BOM_Supplier Part") "Cherry MX or Alps/Matias switch"))
      (libsource (lib "") (part "MX Switch"))
    )
    (comp (ref "SW49")
      (value "MX Switch")
      (fields (field (name "BOM_Supplier Part") "Cherry MX or Alps/Matias switch"))
      (libsource (lib "") (part "MX Switch"))
    )
    (comp (ref "SW50")
      (value "MX Switch")
      (fields (field (name "BOM_Supplier Part") "Cherry MX or Alps/Matias switch"))
      (libsource (lib "") (part "MX Switch"))
    )
    (comp (ref "SW51")
      (value "MX Switch")
      (fields (field (name "BOM_Supplier Part") "Cherry MX or Alps/Matias switch"))
      (libsource (lib "") (part "MX Switch"))
    )
    (comp (ref "SW52")
      (value "MX Switch")
      (fields (field (name "BOM_Supplier Part") "Cherry MX or Alps/Matias switch"))
      (libsource (lib "") (part "MX Switch"))
    )
    (comp (ref "SW53")
      (value "MX Switch")
      (fields (field (name "BOM_Supplier Part") "Cherry MX or Alps/Matias switch"))
      (libsource (lib "") (part "MX Switch"))
    )
    (comp (ref "SW54")
      (value "MX Switch")
      (fields (field (name "BOM_Supplier Part") "Cherry MX or Alps/Matias switch"))
      (libsource (lib "") (part "MX Switch"))
    )
    (comp (ref "SW55")
      (value "MX Switch")
      (fields (field (name "BOM_Supplier Part") "Cherry MX or Alps/Matias switch"))
      (libsource (lib "") (part "MX Switch"))
    )
    (comp (ref "SW56")
      (value "MX Switch")
      (fields (field (name "BOM_Supplier Part") "Cherry MX or Alps/Matias switch"))
      (libsource (lib "") (part "MX Switch"))
    )
    (comp (ref "SW57")
      (value "MX Switch")
      (fields (field (name "BOM_Supplier Part") "Cherry MX or Alps/Matias switch"))
      (libsource (lib "") (part "MX Switch"))
    )
    (comp (ref "SW58")
      (value "MX Switch")
      (fields (field (name "BOM_Supplier Part") "Cherry MX or Alps/Matias switch"))
      (libsource (lib "") (part "MX Switch"))
    )
    (comp (ref "SW59")
      (value "MX Switch")
      (fields (field (name "BOM_Supplier Part") "Cherry MX or Alps/Matias switch"))
      (libsource (lib "") (part "MX Switch"))
    )
    (comp (ref "SW60")
      (value "MX Switch")
      (fields (field (name "BOM_Supplier Part") "Cherry MX or Alps/Matias switch"))
      (libsource (lib "") (part "MX Switch"))
    )
    (comp (ref "SW61")
      (value "MX Switch")
      (fields (field (name "BOM_Supplier Part") "Cherry MX or Alps/Matias switch"))
      (libsource (lib "") (part "MX Switch"))
    )
    (comp (ref "SW62")
      (value "MX Switch")
      (fields (field (name "BOM_Supplier Part") "Cherry MX or Alps/Matias switch"))
      (libsource (lib "") (part "MX Switch"))
    )
    (comp (ref "SW63")
      (value "MX Switch")
      (fields (field (name "BOM_Supplier Part") "Cherry MX or Alps/Matias switch"))
      (libsource (lib "") (part "MX Switch"))
    )
    (comp (ref "SW64")
      (value "MX Switch")
      (fields (field (name "BOM_Supplier Part") "Cherry MX or Alps/Matias switch"))
      (libsource (lib "") (part "MX Switch"))
    )
    (comp (ref "SW65")
      (value "MX Switch")
      (fields (field (name "BOM_Supplier Part") "Cherry MX or Alps/Matias switch"))
      (libsource (lib "") (part "MX Switch"))
    )
    (comp (ref "SW66")
      (value "MX Switch")
      (fields (field (name "BOM_Supplier Part") "Cherry MX or Alps/Matias switch"))
      (libsource (lib "") (part "MX Switch"))
    )
    (comp (ref "SW67")
      (value "MX Switch")
      (fields (field (name "BOM_Supplier Part") "Cherry MX or Alps/Matias switch"))
      (libsource (lib "") (part "MX Switch"))
    )
    (comp (ref "SW68")
      (value "MX Switch")
      (fields (field (name "BOM_Supplier Part") "Cherry MX or Alps/Matias switch"))
      (libsource (lib "") (part "MX Switch"))
    )
    (comp (ref "SW69")
      (value "MX Switch")
      (fields (field (name "BOM_Supplier Part") "Cherry MX or Alps/Matias switch"))
      (libsource (lib "") (part "MX Switch"))
    )
    (comp (ref "SW70")
      (value "MX Switch")
      (fields (field (name "BOM_Supplier Part") "Cherry MX or Alps/Matias switch"))
      (libsource (lib "") (part "MX Switch"))
    )
    (comp (ref "SW71")
      (value "MX Switch")
      (fields (field (name "BOM_Supplier Part") "Cherry MX or Alps/Matias switch"))
      (libsource (lib "") (part "MX Switch"))
    )
  )
  (nets
    (net (code "1") (name "BLED") (class "Default")
      (node (ref "DIP") (pin "1") (pinfunction "A1_1") (pintype "input"))
      (node (ref "SW1") (pin "3") (pinfunction "LED_3") (pintype "unspecified"))
      (node (ref "SW10") (pin "3") (pinfunction "LED_3") (pintype "unspecified"))
      (node (ref "SW11") (pin "3") (pinfunction "LED_3") (pintype "unspecified"))
      (node (ref "SW12") (pin "3") (pinfunction "LED_3") (pintype "unspecified"))
      (node (ref "SW13") (pin "3") (pinfunction "LED_3") (pintype "unspecified"))
      (node (ref "SW14") (pin "3") (pinfunction "LED_3") (pintype "unspecified"))
      (node (ref "SW15") (pin "3") (pinfunction "LED_3") (pintype "unspecified"))
      (node (ref "SW16") (pin "3") (pinfunction "LED_3") (pintype "unspecified"))
      (node (ref "SW17") (pin "3") (pinfunction "LED_3") (pintype "unspecified"))
      (node (ref "SW18") (pin "3") (pinfunction "LED_3") (pintype "unspecified"))
      (node (ref "SW19") (pin "3") (pinfunction "LED_3") (pintype "unspecified"))
      (node (ref "SW2") (pin "3") (pinfunction "LED_3") (pintype "unspecified"))
      (node (ref "SW20") (pin "3") (pinfunction "LED_3") (pintype "unspecified"))
      (node (ref "SW21") (pin "3") (pinfunction "LED_3") (pintype "unspecified"))
      (node (ref "SW22") (pin "3") (pinfunction "LED_3") (pintype "unspecified"))
      (node (ref "SW23") (pin "3") (pinfunction "LED_3") (pintype "unspecified"))
      (node (ref "SW24") (pin "3") (pinfunction "LED_3") (pintype "unspecified"))
      (node (ref "SW25") (pin "3") (pinfunction "LED_3") (pintype "unspecified"))
      (node (ref "SW26") (pin "3") (pinfunction "LED_3") (pintype "unspecified"))
      (node (ref "SW27") (pin "3") (pinfunction "LED_3") (pintype "unspecified"))
      (node (ref "SW28") (pin "3") (pinfunction "LED_3") (pintype "unspecified"))
      (node (ref "SW29") (pin "3") (pinfunction "LED_3") (pintype "unspecified"))
      (node (ref "SW3") (pin "3") (pinfunction "LED_3") (pintype "unspecified"))
      (node (ref "SW30") (pin "3") (pinfunction "LED_3") (pintype "unspecified"))
      (node (ref "SW31") (pin "3") (pinfunction "LED_3") (pintype "unspecified"))
      (node (ref "SW32") (pin "3") (pinfunction "LED_3") (pintype "unspecified"))
      (node (ref "SW33") (pin "3") (pinfunction "LED_3") (pintype "unspecified"))
      (node (ref "SW34") (pin "3") (pinfunction "LED_3") (pintype "unspecified"))
      (node (ref "SW35") (pin "3") (pinfunction "LED_3") (pintype "unspecified"))
      (node (ref "SW36") (pin "3") (pinfunction "LED_3") (pintype "unspecified"))
      (node (ref "SW37") (pin "3") (pinfunction "LED_3") (pintype "unspecified"))
      (node (ref "SW38") (pin "3") (pinfunction "LED_3") (pintype "unspecified"))
      (node (ref "SW39") (pin "3") (pinfunction "LED_3") (pintype "unspecified"))
      (node (ref "SW4") (pin "3") (pinfunction "LED_3") (pintype "unspecified"))
      (node (ref "SW40") (pin "3") (pinfunction "LED_3") (pintype "unspecified"))
      (node (ref "SW41") (pin "3") (pinfunction "LED_3") (pintype "unspecified"))
      (node (ref "SW42") (pin "3") (pinfunction "LED_3") (pintype "unspecified"))
      (node (ref "SW43") (pin "3") (pinfunction "LED_3") (pintype "unspecified"))
      (node (ref "SW44") (pin "3") (pinfunction "LED_3") (pintype "unspecified"))
      (node (ref "SW45") (pin "3") (pinfunction "LED_3") (pintype "unspecified"))
      (node (ref "SW46") (pin "3") (pinfunction "LED_3") (pintype "unspecified"))
      (node (ref "SW47") (pin "3") (pinfunction "LED_3") (pintype "unspecified"))
      (node (ref "SW48") (pin "3") (pinfunction "LED_3") (pintype "unspecified"))
      (node (ref "SW49") (pin "3") (pinfunction "LED_3") (pintype "unspecified"))
      (node (ref "SW5") (pin "3") (pinfunction "LED_3") (pintype "unspecified"))
      (node (ref "SW50") (pin "3") (pinfunction "LED_3") (pintype "unspecified"))
      (node (ref "SW51") (pin "3") (pinfunction "LED_3") (pintype "unspecified"))
      (node (ref "SW52") (pin "3") (pinfunction "LED_3") (pintype "unspecified"))
      (node (ref "SW53") (pin "3") (pinfunction "LED_3") (pintype "unspecified"))
      (node (ref "SW54") (pin "3") (pinfunction "LED_3") (pintype "unspecified"))
      (node (ref "SW55") (pin "3") (pinfunction "LED_3") (pintype "unspecified"))
      (node (ref "SW56") (pin "3") (pinfunction "LED_3") (pintype "unspecified"))
      (node (ref "SW57") (pin "3") (pinfunction "LED_3") (pintype "unspecified"))
      (node (ref "SW58") (pin "3") (pinfunction "LED_3") (pintype "unspecified"))
      (node (ref "SW59") (pin "3") (pinfunction "LED_3") (pintype "unspecified"))
      (node (ref "SW6") (pin "3") (pinfunction "LED_3") (pintype "unspecified"))
      (node (ref "SW60") (pin "3") (pinfunction "LED_3") (pintype "unspecified"))
      (node (ref "SW61") (pin "3") (pinfunction "LED_3") (pintype "unspecified"))
      (node (ref "SW62") (pin "3") (pinfunction "LED_3") (pintype "unspecified"))
      (node (ref "SW63") (pin "3") (pinfunction "LED_3") (pintype "unspecified"))
      (node (ref "SW64") (pin "3") (pinfunction "LED_3") (pintype "unspecified"))
      (node (ref "SW65") (pin "3") (pinfunction "LED_3") (pintype "unspecified"))
      (node (ref "SW66") (pin "3") (pinfunction "LED_3") (pintype "unspecified"))
      (node (ref "SW67") (pin "3") (pinfunction "LED_3") (pintype "unspecified"))
      (node (ref "SW68") (pin "3") (pinfunction "LED_3") (pintype "unspecified"))
      (node (ref "SW69") (pin "3") (pinfunction "LED_3") (pintype "unspecified"))
      (node (ref "SW7") (pin "3") (pinfunction "LED_3") (pintype "unspecified"))
      (node (ref "SW70") (pin "3") (pinfunction "LED_3") (pintype "unspecified"))
      (node (ref "SW71") (pin "3") (pinfunction "LED_3") (pintype "unspecified"))
      (node (ref "SW8") (pin "3") (pinfunction "LED_3") (pintype "unspecified"))
      (node (ref "SW9") (pin "3") (pinfunction "LED_3") (pintype "unspecified"))
    )
    (net (code "2") (name "Col0") (class "Default")
      (node (ref "SW1") (pin "1") (pinfunction "Col_1") (pintype "unspecified"))
      (node (ref "SW2") (pin "1") (pinfunction "Col_1") (pintype "unspecified"))
      (node (ref "SW3") (pin "1") (pinfunction "Col_1") (pintype "unspecified"))
      (node (ref "SW4") (pin "1") (pinfunction "Col_1") (pintype "unspecified"))
      (node (ref "SW5") (pin "1") (pinfunction "Col_1") (pintype "unspecified"))
      (node (ref "U1") (pin "22") (pinfunction "PD5(XCK1/CTS#)_22") (pintype "unspecified"))
    )
    (net (code "3") (name "Col1") (class "Default")
      (node (ref "SW10") (pin "1") (pinfunction "Col_1") (pintype "unspecified"))
      (node (ref "SW6") (pin "1") (pinfunction "Col_1") (pintype "unspecified"))
      (node (ref "SW7") (pin "1") (pinfunction "Col_1") (pintype "unspecified"))
      (node (ref "SW8") (pin "1") (pinfunction "Col_1") (pintype "unspecified"))
      (node (ref "SW9") (pin "1") (pinfunction "Col_1") (pintype "unspecified"))
      (node (ref "U1") (pin "21") (pinfunction "PD3(TXD1/INT3)_21") (pintype "unspecified"))
    )
    (net (code "4") (name "Col2") (class "Default")
      (node (ref "SW11") (pin "1") (pinfunction "Col_1") (pintype "unspecified"))
      (node (ref "SW12") (pin "1") (pinfunction "Col_1") (pintype "unspecified"))
      (node (ref "SW13") (pin "1") (pinfunction "Col_1") (pintype "unspecified"))
      (node (ref "SW14") (pin "1") (pinfunction "Col_1") (pintype "unspecified"))
      (node (ref "SW15") (pin "1") (pinfunction "Col_1") (pintype "unspecified"))
      (node (ref "U1") (pin "20") (pinfunction "PD2(RXD1/INT2)_20") (pintype "unspecified"))
    )
    (net (code "5") (name "Col3") (class "Default")
      (node (ref "SW16") (pin "1") (pinfunction "Col_1") (pintype "unspecified"))
      (node (ref "SW17") (pin "1") (pinfunction "Col_1") (pintype "unspecified"))
      (node (ref "SW18") (pin "1") (pinfunction "Col_1") (pintype "unspecified"))
      (node (ref "SW19") (pin "1") (pinfunction "Col_1") (pintype "unspecified"))
      (node (ref "SW20") (pin "1") (pinfunction "Col_1") (pintype "unspecified"))
      (node (ref "U1") (pin "40") (pinfunction "PF1(ADC1)_40") (pintype "unspecified"))
    )
    (net (code "6") (name "Col4") (class "Default")
      (node (ref "SW21") (pin "1") (pinfunction "Col_1") (pintype "unspecified"))
      (node (ref "SW22") (pin "1") (pinfunction "Col_1") (pintype "unspecified"))
      (node (ref "SW23") (pin "1") (pinfunction "Col_1") (pintype "unspecified"))
      (node (ref "SW24") (pin "1") (pinfunction "Col_1") (pintype "unspecified"))
      (node (ref "SW25") (pin "1") (pinfunction "Col_1") (pintype "unspecified"))
      (node (ref "U1") (pin "39") (pinfunction "PF4(ADC4/TCK)_39") (pintype "unspecified"))
    )
    (net (code "7") (name "Col5") (class "Default")
      (node (ref "SW26") (pin "1") (pinfunction "Col_1") (pintype "unspecified"))
      (node (ref "SW27") (pin "1") (pinfunction "Col_1") (pintype "unspecified"))
      (node (ref "SW28") (pin "1") (pinfunction "Col_1") (pintype "unspecified"))
      (node (ref "SW29") (pin "1") (pinfunction "Col_1") (pintype "unspecified"))
      (node (ref "SW30") (pin "1") (pinfunction "Col_1") (pintype "unspecified"))
      (node (ref "U1") (pin "38") (pinfunction "PF5(ADC5/TMS)_38") (pintype "unspecified"))
    )
    (net (code "8") (name "Col6") (class "Default")
      (node (ref "SW31") (pin "1") (pinfunction "Col_1") (pintype "unspecified"))
      (node (ref "SW32") (pin "1") (pinfunction "Col_1") (pintype "unspecified"))
      (node (ref "SW33") (pin "1") (pinfunction "Col_1") (pintype "unspecified"))
      (node (ref "SW34") (pin "1") (pinfunction "Col_1") (pintype "unspecified"))
      (node (ref "SW35") (pin "1") (pinfunction "Col_1") (pintype "unspecified"))
      (node (ref "SW36") (pin "1") (pinfunction "Col_1") (pintype "unspecified"))
      (node (ref "SW37") (pin "1") (pinfunction "Col_1") (pintype "unspecified"))
      (node (ref "U1") (pin "37") (pinfunction "PF6(ADC6/TDO)_37") (pintype "unspecified"))
    )
    (net (code "9") (name "Col7") (class "Default")
      (node (ref "SW38") (pin "1") (pinfunction "Col_1") (pintype "unspecified"))
      (node (ref "SW39") (pin "1") (pinfunction "Col_1") (pintype "unspecified"))
      (node (ref "SW40") (pin "1") (pinfunction "Col_1") (pintype "unspecified"))
      (node (ref "SW41") (pin "1") (pinfunction "Col_1") (pintype "unspecified"))
      (node (ref "SW42") (pin "1") (pinfunction "Col_1") (pintype "unspecified"))
      (node (ref "U1") (pin "36") (pinfunction "PF7(ADC7/TDI)_36") (pintype "unspecified"))
    )
    (net (code "10") (name "Col8") (class "Default")
      (node (ref "SW43") (pin "1") (pinfunction "Col_1") (pintype "unspecified"))
      (node (ref "SW44") (pin "1") (pinfunction "Col_1") (pintype "unspecified"))
      (node (ref "SW45") (pin "1") (pinfunction "Col_1") (pintype "unspecified"))
      (node (ref "SW46") (pin "1") (pinfunction "Col_1") (pintype "unspecified"))
      (node (ref "SW47") (pin "1") (pinfunction "Col_1") (pintype "unspecified"))
      (node (ref "U1") (pin "32") (pinfunction "PC7(ICP3/CLK0/OC4A)_32") (pintype "unspecified"))
    )
    (net (code "11") (name "Col9") (class "Default")
      (node (ref "SW48") (pin "1") (pinfunction "Col_1") (pintype "unspecified"))
      (node (ref "SW49") (pin "1") (pinfunction "Col_1") (pintype "unspecified"))
      (node (ref "SW50") (pin "1") (pinfunction "Col_1") (pintype "unspecified"))
      (node (ref "SW51") (pin "1") (pinfunction "Col_1") (pintype "unspecified"))
      (node (ref "SW52") (pin "1") (pinfunction "Col_1") (pintype "unspecified"))
      (node (ref "U1") (pin "31") (pinfunction "PC6(OC3A/OC4A#)_31") (pintype "unspecified"))
    )
    (net (code "12") (name "Col10") (class "Default")
      (node (ref "SW53") (pin "1") (pinfunction "Col_1") (pintype "unspecified"))
      (node (ref "SW54") (pin "1") (pinfunction "Col_1") (pintype "unspecified"))
      (node (ref "SW55") (pin "1") (pinfunction "Col_1") (pintype "unspecified"))
      (node (ref "SW56") (pin "1") (pinfunction "Col_1") (pintype "unspecified"))
      (node (ref "SW57") (pin "1") (pinfunction "Col_1") (pintype "unspecified"))
      (node (ref "U1") (pin "30") (pinfunction "PB6(PCINT6/OC1B/OC4B/ADC13)_30") (pintype "unspecified"))
    )
    (net (code "13") (name "Col11") (class "Default")
      (node (ref "SW58") (pin "1") (pinfunction "Col_1") (pintype "unspecified"))
      (node (ref "SW59") (pin "1") (pinfunction "Col_1") (pintype "unspecified"))
      (node (ref "SW60") (pin "1") (pinfunction "Col_1") (pintype "unspecified"))
      (node (ref "SW61") (pin "1") (pinfunction "Col_1") (pintype "unspecified"))
      (node (ref "SW62") (pin "1") (pinfunction "Col_1") (pintype "unspecified"))
      (node (ref "U1") (pin "29") (pinfunction "PB5(PCINT5/OC1A/OC4B#/ADC12)_29") (pintype "unspecified"))
    )
    (net (code "14") (name "Col12") (class "Default")
      (node (ref "SW63") (pin "1") (pinfunction "Col_1") (pintype "unspecified"))
      (node (ref "SW64") (pin "1") (pinfunction "Col_1") (pintype "unspecified"))
      (node (ref "SW65") (pin "1") (pinfunction "Col_1") (pintype "unspecified"))
      (node (ref "SW66") (pin "1") (pinfunction "Col_1") (pintype "unspecified"))
      (node (ref "SW67") (pin "1") (pinfunction "Col_1") (pintype "unspecified"))
      (node (ref "U1") (pin "28") (pinfunction "PB4(PCINT4/ADC11)_28") (pintype "unspecified"))
    )
    (net (code "15") (name "Col13") (class "Default")
      (node (ref "ENC1") (pin "E") (pinfunction "E_E") (pintype "unspecified"))
      (node (ref "SW68") (pin "1") (pinfunction "Col_1") (pintype "unspecified"))
      (node (ref "SW69") (pin "1") (pinfunction "Col_1") (pintype "unspecified"))
      (node (ref "SW70") (pin "1") (pinfunction "Col_1") (pintype "unspecified"))
      (node (ref "SW71") (pin "1") (pinfunction "Col_1") (pintype "unspecified"))
      (node (ref "U1") (pin "27") (pinfunction "PD7(T0/OC4D/ADC10)_27") (pintype "unspecified"))
    )
    (net (code "16") (name "Din_N") (class "Default")
      (node (ref "ESD1") (pin "3") (pinfunction "I/O2_3") (pintype "unspecified"))
      (node (ref "USBC1") (pin "A7") (pinfunction "DN1_A7") (pintype "unspecified"))
      (node (ref "USBC1") (pin "B7") (pinfunction "DN2_B7") (pintype "unspecified"))
    )
    (net (code "17") (name "Din_P") (class "Default")
      (node (ref "ESD1") (pin "1") (pinfunction "I/O1_1") (pintype "unspecified"))
      (node (ref "USBC1") (pin "A6") (pinfunction "DP1_A6") (pintype "unspecified"))
      (node (ref "USBC1") (pin "B6") (pinfunction "DP2_B6") (pintype "unspecified"))
    )
    (net (code "18") (name "Dout_N") (class "Default")
      (node (ref "ESD1") (pin "4") (pinfunction "I/O2_4") (pintype "unspecified"))
      (node (ref "R70") (pin "2") (pinfunction "2_2") (pintype "input"))
    )
    (net (code "19") (name "Dout_P") (class "Default")
      (node (ref "ESD1") (pin "6") (pinfunction "I/O1_6") (pintype "unspecified"))
      (node (ref "R71") (pin "2") (pinfunction "2_2") (pintype "input"))
    )
    (net (code "20") (name "GND") (class "Default")
      (node (ref "BUTTON") (pin "3") (pinfunction "C_3") (pintype "unspecified"))
      (node (ref "BUTTON") (pin "4") (pinfunction "D_4") (pintype "unspecified"))
      (node (ref "C1") (pin "2") (pinfunction "2_2") (pintype "unspecified"))
      (node (ref "C10") (pin "1") (pinfunction "1_1") (pintype "input"))
      (node (ref "C11") (pin "1") (pinfunction "1_1") (pintype "input"))
      (node (ref "C12") (pin "1") (pinfunction "1_1") (pintype "input"))
      (node (ref "C2") (pin "1") (pinfunction "1_1") (pintype "unspecified"))
      (node (ref "C3") (pin "1") (pinfunction "1_1") (pintype "unspecified"))
      (node (ref "C4") (pin "1") (pinfunction "1_1") (pintype "unspecified"))
      (node (ref "C5") (pin "1") (pinfunction "1_1") (pintype "unspecified"))
      (node (ref "C6") (pin "1") (pinfunction "1_1") (pintype "unspecified"))
      (node (ref "C7") (pin "1") (pinfunction "1_1") (pintype "input"))
      (node (ref "C8") (pin "1") (pinfunction "1_1") (pintype "unspecified"))
      (node (ref "C9") (pin "2") (pinfunction "2_2") (pintype "unspecified"))
      (node (ref "DIP") (pin "2") (pinfunction "A2_2") (pintype "input"))
      (node (ref "ENC1") (pin "C") (pinfunction "C_C") (pintype "unspecified"))
      (node (ref "ESD1") (pin "2") (pinfunction "GND_2") (pintype "unspecified"))
      (node (ref "OLED1") (pin "4") (pinfunction "GND_4") (pintype "unspecified"))
      (node (ref "R1") (pin "1") (pinfunction "1_1") (pintype "unspecified"))
      (node (ref "R10") (pin "1") (pinfunction "1_1") (pintype "unspecified"))
      (node (ref "R11") (pin "1") (pinfunction "1_1") (pintype "unspecified"))
      (node (ref "R12") (pin "1") (pinfunction "1_1") (pintype "unspecified"))
      (node (ref "R13") (pin "1") (pinfunction "1_1") (pintype "unspecified"))
      (node (ref "R14") (pin "1") (pinfunction "1_1") (pintype "unspecified"))
      (node (ref "R15") (pin "1") (pinfunction "1_1") (pintype "unspecified"))
      (node (ref "R16") (pin "1") (pinfunction "1_1") (pintype "unspecified"))
      (node (ref "R17") (pin "1") (pinfunction "1_1") (pintype "unspecified"))
      (node (ref "R18") (pin "1") (pinfunction "1_1") (pintype "unspecified"))
      (node (ref "R19") (pin "1") (pinfunction "1_1") (pintype "unspecified"))
      (node (ref "R2") (pin "1") (pinfunction "1_1") (pintype "unspecified"))
      (node (ref "R20") (pin "1") (pinfunction "1_1") (pintype "unspecified"))
      (node (ref "R21") (pin "1") (pinfunction "1_1") (pintype "unspecified"))
      (node (ref "R22") (pin "1") (pinfunction "1_1") (pintype "unspecified"))
      (node (ref "R23") (pin "1") (pinfunction "1_1") (pintype "unspecified"))
      (node (ref "R24") (pin "1") (pinfunction "1_1") (pintype "unspecified"))
      (node (ref "R25") (pin "1") (pinfunction "1_1") (pintype "unspecified"))
      (node (ref "R26") (pin "1") (pinfunction "1_1") (pintype "unspecified"))
      (node (ref "R27") (pin "1") (pinfunction "1_1") (pintype "unspecified"))
      (node (ref "R28") (pin "1") (pinfunction "1_1") (pintype "unspecified"))
      (node (ref "R29") (pin "1") (pinfunction "1_1") (pintype "unspecified"))
      (node (ref "R3") (pin "1") (pinfunction "1_1") (pintype "unspecified"))
      (node (ref "R30") (pin "1") (pinfunction "1_1") (pintype "unspecified"))
      (node (ref "R31") (pin "1") (pinfunction "1_1") (pintype "unspecified"))
      (node (ref "R32") (pin "1") (pinfunction "1_1") (pintype "unspecified"))
      (node (ref "R33") (pin "1") (pinfunction "1_1") (pintype "unspecified"))
      (node (ref "R34") (pin "1") (pinfunction "1_1") (pintype "unspecified"))
      (node (ref "R35") (pin "1") (pinfunction "1_1") (pintype "unspecified"))
      (node (ref "R36") (pin "1") (pinfunction "1_1") (pintype "unspecified"))
      (node (ref "R37") (pin "1") (pinfunction "1_1") (pintype "unspecified"))
      (node (ref "R38") (pin "1") (pinfunction "1_1") (pintype "unspecified"))
      (node (ref "R39") (pin "1") (pinfunction "1_1") (pintype "unspecified"))
      (node (ref "R4") (pin "1") (pinfunction "1_1") (pintype "unspecified"))
      (node (ref "R40") (pin "1") (pinfunction "1_1") (pintype "unspecified"))
      (node (ref "R41") (pin "1") (pinfunction "1_1") (pintype "unspecified"))
      (node (ref "R42") (pin "1") (pinfunction "1_1") (pintype "unspecified"))
      (node (ref "R43") (pin "1") (pinfunction "1_1") (pintype "unspecified"))
      (node (ref "R44") (pin "1") (pinfunction "1_1") (pintype "unspecified"))
      (node (ref "R45") (pin "1") (pinfunction "1_1") (pintype "unspecified"))
      (node (ref "R46") (pin "1") (pinfunction "1_1") (pintype "unspecified"))
      (node (ref "R47") (pin "1") (pinfunction "1_1") (pintype "unspecified"))
      (node (ref "R48") (pin "1") (pinfunction "1_1") (pintype "unspecified"))
      (node (ref "R49") (pin "1") (pinfunction "1_1") (pintype "unspecified"))
      (node (ref "R5") (pin "1") (pinfunction "1_1") (pintype "unspecified"))
      (node (ref "R50") (pin "1") (pinfunction "1_1") (pintype "unspecified"))
      (node (ref "R51") (pin "1") (pinfunction "1_1") (pintype "unspecified"))
      (node (ref "R52") (pin "1") (pinfunction "1_1") (pintype "unspecified"))
      (node (ref "R53") (pin "1") (pinfunction "1_1") (pintype "unspecified"))
      (node (ref "R54") (pin "1") (pinfunction "1_1") (pintype "unspecified"))
      (node (ref "R55") (pin "1") (pinfunction "1_1") (pintype "unspecified"))
      (node (ref "R56") (pin "1") (pinfunction "1_1") (pintype "unspecified"))
      (node (ref "R57") (pin "1") (pinfunction "1_1") (pintype "unspecified"))
      (node (ref "R58") (pin "1") (pinfunction "1_1") (pintype "unspecified"))
      (node (ref "R59") (pin "1") (pinfunction "1_1") (pintype "unspecified"))
      (node (ref "R6") (pin "1") (pinfunction "1_1") (pintype "unspecified"))
      (node (ref "R60") (pin "1") (pinfunction "1_1") (pintype "unspecified"))
      (node (ref "R61") (pin "1") (pinfunction "1_1") (pintype "unspecified"))
      (node (ref "R62") (pin "1") (pinfunction "1_1") (pintype "unspecified"))
      (node (ref "R63") (pin "1") (pinfunction "1_1") (pintype "unspecified"))
      (node (ref "R64") (pin "1") (pinfunction "1_1") (pintype "unspecified"))
      (node (ref "R65") (pin "1") (pinfunction "1_1") (pintype "unspecified"))
      (node (ref "R66") (pin "1") (pinfunction "1_1") (pintype "unspecified"))
      (node (ref "R67") (pin "1") (pinfunction "1_1") (pintype "unspecified"))
      (node (ref "R68") (pin "1") (pinfunction "1_1") (pintype "unspecified"))
      (node (ref "R69") (pin "1") (pinfunction "1_1") (pintype "unspecified"))
      (node (ref "R7") (pin "1") (pinfunction "1_1") (pintype "unspecified"))
      (node (ref "R72") (pin "1") (pinfunction "1_1") (pintype "input"))
      (node (ref "R73") (pin "1") (pinfunction "1_1") (pintype "unspecified"))
      (node (ref "R74") (pin "2") (pinfunction "2_2") (pintype "unspecified"))
      (node (ref "R75") (pin "1") (pinfunction "1_1") (pintype "unspecified"))
      (node (ref "R8") (pin "1") (pinfunction "1_1") (pintype "unspecified"))
      (node (ref "R9") (pin "1") (pinfunction "1_1") (pintype "unspecified"))
      (node (ref "STO1") (pin "1") (pinfunction "Standoff_1") (pintype "unspecified"))
      (node (ref "STO2") (pin "1") (pinfunction "Standoff_1") (pintype "unspecified"))
      (node (ref "STO3") (pin "1") (pinfunction "Standoff_1") (pintype "unspecified"))
      (node (ref "STO4") (pin "1") (pinfunction "Standoff_1") (pintype "unspecified"))
      (node (ref "STO5") (pin "1") (pinfunction "Standoff_1") (pintype "unspecified"))
      (node (ref "STO6") (pin "1") (pinfunction "Standoff_1") (pintype "unspecified"))
      (node (ref "STO7") (pin "1") (pinfunction "Standoff_1") (pintype "unspecified"))
      (node (ref "U1") (pin "15") (pinfunction "GND_15") (pintype "unspecified"))
      (node (ref "U1") (pin "23") (pinfunction "GND_23") (pintype "unspecified"))
      (node (ref "U1") (pin "35") (pinfunction "GND_35") (pintype "unspecified"))
      (node (ref "U1") (pin "43") (pinfunction "GND_43") (pintype "unspecified"))
      (node (ref "U1") (pin "45") (pinfunction "EP_45") (pintype "unspecified"))
      (node (ref "U1") (pin "5") (pinfunction "UGnd_5") (pintype "unspecified"))
      (node (ref "U2") (pin "4") (pinfunction "._4") (pintype "unspecified"))
      (node (ref "USBC1") (pin "A1") (pinfunction "GND_A1") (pintype "unspecified"))
      (node (ref "USBC1") (pin "A12") (pinfunction "GND_A12") (pintype "unspecified"))
      (node (ref "X1") (pin "2") (pinfunction "GND_2") (pintype "unspecified"))
      (node (ref "X1") (pin "4") (pinfunction "GND_4") (pintype "unspecified"))
    )
    (net (code "21") (name "Net-(D1-A)") (class "Default")
      (node (ref "D1") (pin "2") (pinfunction "A_2") (pintype "unspecified"))
      (node (ref "SW1") (pin "2") (pinfunction "Row_2") (pintype "unspecified"))
    )
    (net (code "22") (name "Net-(D2-A)") (class "Default")
      (node (ref "D2") (pin "2") (pinfunction "A_2") (pintype "unspecified"))
      (node (ref "SW2") (pin "2") (pinfunction "Row_2") (pintype "unspecified"))
    )
    (net (code "23") (name "Net-(D3-A)") (class "Default")
      (node (ref "D3") (pin "2") (pinfunction "A_2") (pintype "unspecified"))
      (node (ref "SW3") (pin "2") (pinfunction "Row_2") (pintype "unspecified"))
    )
    (net (code "24") (name "Net-(D4-A)") (class "Default")
      (node (ref "D4") (pin "2") (pinfunction "A_2") (pintype "unspecified"))
      (node (ref "SW4") (pin "2") (pinfunction "Row_2") (pintype "unspecified"))
    )
    (net (code "25") (name "Net-(D5-A)") (class "Default")
      (node (ref "D5") (pin "2") (pinfunction "A_2") (pintype "unspecified"))
      (node (ref "SW5") (pin "2") (pinfunction "Row_2") (pintype "unspecified"))
    )
    (net (code "26") (name "Net-(D6-A)") (class "Default")
      (node (ref "D6") (pin "2") (pinfunction "A_2") (pintype "unspecified"))
      (node (ref "SW6") (pin "2") (pinfunction "Row_2") (pintype "unspecified"))
    )
    (net (code "27") (name "Net-(D7-A)") (class "Default")
      (node (ref "D7") (pin "2") (pinfunction "A_2") (pintype "unspecified"))
      (node (ref "SW7") (pin "2") (pinfunction "Row_2") (pintype "unspecified"))
    )
    (net (code "28") (name "Net-(D8-A)") (class "Default")
      (node (ref "D8") (pin "2") (pinfunction "A_2") (pintype "unspecified"))
      (node (ref "SW8") (pin "2") (pinfunction "Row_2") (pintype "unspecified"))
    )
    (net (code "29") (name "Net-(D9-A)") (class "Default")
      (node (ref "D9") (pin "2") (pinfunction "A_2") (pintype "unspecified"))
      (node (ref "SW9") (pin "2") (pinfunction "Row_2") (pintype "unspecified"))
    )
    (net (code "30") (name "Net-(D10-A)") (class "Default")
      (node (ref "D10") (pin "2") (pinfunction "A_2") (pintype "unspecified"))
      (node (ref "SW10") (pin "2") (pinfunction "Row_2") (pintype "unspecified"))
    )
    (net (code "31") (name "Net-(D11-A)") (class "Default")
      (node (ref "D11") (pin "2") (pinfunction "A_2") (pintype "unspecified"))
      (node (ref "SW11") (pin "2") (pinfunction "Row_2") (pintype "unspecified"))
    )
    (net (code "32") (name "Net-(D12-A)") (class "Default")
      (node (ref "D12") (pin "2") (pinfunction "A_2") (pintype "unspecified"))
      (node (ref "SW12") (pin "2") (pinfunction "Row_2") (pintype "unspecified"))
    )
    (net (code "33") (name "Net-(D13-A)") (class "Default")
      (node (ref "D13") (pin "2") (pinfunction "A_2") (pintype "unspecified"))
      (node (ref "SW13") (pin "2") (pinfunction "Row_2") (pintype "unspecified"))
    )
    (net (code "34") (name "Net-(D14-A)") (class "Default")
      (node (ref "D14") (pin "2") (pinfunction "A_2") (pintype "unspecified"))
      (node (ref "SW14") (pin "2") (pinfunction "Row_2") (pintype "unspecified"))
    )
    (net (code "35") (name "Net-(D15-A)") (class "Default")
      (node (ref "D15") (pin "2") (pinfunction "A_2") (pintype "unspecified"))
      (node (ref "SW15") (pin "2") (pinfunction "Row_2") (pintype "unspecified"))
    )
    (net (code "36") (name "Net-(D16-A)") (class "Default")
      (node (ref "D16") (pin "2") (pinfunction "A_2") (pintype "unspecified"))
      (node (ref "SW16") (pin "2") (pinfunction "Row_2") (pintype "unspecified"))
    )
    (net (code "37") (name "Net-(D17-A)") (class "Default")
      (node (ref "D17") (pin "2") (pinfunction "A_2") (pintype "unspecified"))
      (node (ref "SW17") (pin "2") (pinfunction "Row_2") (pintype "unspecified"))
    )
    (net (code "38") (name "Net-(D18-A)") (class "Default")
      (node (ref "D18") (pin "2") (pinfunction "A_2") (pintype "unspecified"))
      (node (ref "SW18") (pin "2") (pinfunction "Row_2") (pintype "unspecified"))
    )
    (net (code "39") (name "Net-(D19-A)") (class "Default")
      (node (ref "D19") (pin "2") (pinfunction "A_2") (pintype "unspecified"))
      (node (ref "SW19") (pin "2") (pinfunction "Row_2") (pintype "unspecified"))
    )
    (net (code "40") (name "Net-(D20-A)") (class "Default")
      (node (ref "D20") (pin "2") (pinfunction "A_2") (pintype "unspecified"))
      (node (ref "SW20") (pin "2") (pinfunction "Row_2") (pintype "unspecified"))
    )
    (net (code "41") (name "Net-(D21-A)") (class "Default")
      (node (ref "D21") (pin "2") (pinfunction "A_2") (pintype "unspecified"))
      (node (ref "SW21") (pin "2") (pinfunction "Row_2") (pintype "unspecified"))
    )
    (net (code "42") (name "Net-(D22-A)") (class "Default")
      (node (ref "D22") (pin "2") (pinfunction "A_2") (pintype "unspecified"))
      (node (ref "SW22") (pin "2") (pinfunction "Row_2") (pintype "unspecified"))
    )
    (net (code "43") (name "Net-(D23-A)") (class "Default")
      (node (ref "D23") (pin "2") (pinfunction "A_2") (pintype "unspecified"))
      (node (ref "SW23") (pin "2") (pinfunction "Row_2") (pintype "unspecified"))
    )
    (net (code "44") (name "Net-(D24-A)") (class "Default")
      (node (ref "D24") (pin "2") (pinfunction "A_2") (pintype "unspecified"))
      (node (ref "SW24") (pin "2") (pinfunction "Row_2") (pintype "unspecified"))
    )
    (net (code "45") (name "Net-(D25-A)") (class "Default")
      (node (ref "D25") (pin "2") (pinfunction "A_2") (pintype "unspecified"))
      (node (ref "SW25") (pin "2") (pinfunction "Row_2") (pintype "unspecified"))
    )
    (net (code "46") (name "Net-(D26-A)") (class "Default")
      (node (ref "D26") (pin "2") (pinfunction "A_2") (pintype "unspecified"))
      (node (ref "SW26") (pin "2") (pinfunction "Row_2") (pintype "unspecified"))
    )
    (net (code "47") (name "Net-(D27-A)") (class "Default")
      (node (ref "D27") (pin "2") (pinfunction "A_2") (pintype "unspecified"))
      (node (ref "SW27") (pin "2") (pinfunction "Row_2") (pintype "unspecified"))
    )
    (net (code "48") (name "Net-(D28-A)") (class "Default")
      (node (ref "D28") (pin "2") (pinfunction "A_2") (pintype "unspecified"))
      (node (ref "SW28") (pin "2") (pinfunction "Row_2") (pintype "unspecified"))
    )
    (net (code "49") (name "Net-(D29-A)") (class "Default")
      (node (ref "D29") (pin "2") (pinfunction "A_2") (pintype "unspecified"))
      (node (ref "SW29") (pin "2") (pinfunction "Row_2") (pintype "unspecified"))
    )
    (net (code "50") (name "Net-(D30-A)") (class "Default")
      (node (ref "D30") (pin "2") (pinfunction "A_2") (pintype "unspecified"))
      (node (ref "SW30") (pin "2") (pinfunction "Row_2") (pintype "unspecified"))
    )
    (net (code "51") (name "Net-(D31-A)") (class "Default")
      (node (ref "D31") (pin "2") (pinfunction "A_2") (pintype "unspecified"))
      (node (ref "SW31") (pin "2") (pinfunction "Row_2") (pintype "unspecified"))
      (node (ref "SW32") (pin "2") (pinfunction "Row_2") (pintype "unspecified"))
    )
    (net (code "52") (name "Net-(D32-A)") (class "Default")
      (node (ref "D32") (pin "2") (pinfunction "A_2") (pintype "unspecified"))
      (node (ref "SW33") (pin "2") (pinfunction "Row_2") (pintype "unspecified"))
    )
    (net (code "53") (name "Net-(D33-A)") (class "Default")
      (node (ref "D33") (pin "2") (pinfunction "A_2") (pintype "unspecified"))
      (node (ref "SW34") (pin "2") (pinfunction "Row_2") (pintype "unspecified"))
    )
    (net (code "54") (name "Net-(D34-A)") (class "Default")
      (node (ref "D34") (pin "2") (pinfunction "A_2") (pintype "unspecified"))
      (node (ref "SW35") (pin "2") (pinfunction "Row_2") (pintype "unspecified"))
    )
    (net (code "55") (name "Net-(D35-A)") (class "Default")
      (node (ref "D35") (pin "2") (pinfunction "A_2") (pintype "unspecified"))
      (node (ref "SW36") (pin "2") (pinfunction "Row_2") (pintype "unspecified"))
      (node (ref "SW37") (pin "2") (pinfunction "Row_2") (pintype "unspecified"))
    )
    (net (code "56") (name "Net-(D36-A)") (class "Default")
      (node (ref "D36") (pin "2") (pinfunction "A_2") (pintype "unspecified"))
      (node (ref "SW38") (pin "2") (pinfunction "Row_2") (pintype "unspecified"))
    )
    (net (code "57") (name "Net-(D37-A)") (class "Default")
      (node (ref "D37") (pin "2") (pinfunction "A_2") (pintype "unspecified"))
      (node (ref "SW39") (pin "2") (pinfunction "Row_2") (pintype "unspecified"))
    )
    (net (code "58") (name "Net-(D38-A)") (class "Default")
      (node (ref "D38") (pin "2") (pinfunction "A_2") (pintype "unspecified"))
      (node (ref "SW40") (pin "2") (pinfunction "Row_2") (pintype "unspecified"))
    )
    (net (code "59") (name "Net-(D39-A)") (class "Default")
      (node (ref "D39") (pin "2") (pinfunction "A_2") (pintype "unspecified"))
      (node (ref "SW41") (pin "2") (pinfunction "Row_2") (pintype "unspecified"))
    )
    (net (code "60") (name "Net-(D40-A)") (class "Default")
      (node (ref "D40") (pin "2") (pinfunction "A_2") (pintype "unspecified"))
      (node (ref "SW42") (pin "2") (pinfunction "Row_2") (pintype "unspecified"))
    )
    (net (code "61") (name "Net-(D41-A)") (class "Default")
      (node (ref "D41") (pin "2") (pinfunction "A_2") (pintype "unspecified"))
      (node (ref "SW43") (pin "2") (pinfunction "Row_2") (pintype "unspecified"))
    )
    (net (code "62") (name "Net-(D42-A)") (class "Default")
      (node (ref "D42") (pin "2") (pinfunction "A_2") (pintype "unspecified"))
      (node (ref "SW44") (pin "2") (pinfunction "Row_2") (pintype "unspecified"))
    )
    (net (code "63") (name "Net-(D43-A)") (class "Default")
      (node (ref "D43") (pin "2") (pinfunction "A_2") (pintype "unspecified"))
      (node (ref "SW45") (pin "2") (pinfunction "Row_2") (pintype "unspecified"))
    )
    (net (code "64") (name "Net-(D44-A)") (class "Default")
      (node (ref "D44") (pin "2") (pinfunction "A_2") (pintype "unspecified"))
      (node (ref "SW46") (pin "2") (pinfunction "Row_2") (pintype "unspecified"))
    )
    (net (code "65") (name "Net-(D45-A)") (class "Default")
      (node (ref "D45") (pin "2") (pinfunction "A_2") (pintype "unspecified"))
      (node (ref "SW47") (pin "2") (pinfunction "Row_2") (pintype "unspecified"))
    )
    (net (code "66") (name "Net-(D46-A)") (class "Default")
      (node (ref "D46") (pin "2") (pinfunction "A_2") (pintype "unspecified"))
      (node (ref "SW48") (pin "2") (pinfunction "Row_2") (pintype "unspecified"))
    )
    (net (code "67") (name "Net-(D47-A)") (class "Default")
      (node (ref "D47") (pin "2") (pinfunction "A_2") (pintype "unspecified"))
      (node (ref "SW49") (pin "2") (pinfunction "Row_2") (pintype "unspecified"))
    )
    (net (code "68") (name "Net-(D48-A)") (class "Default")
      (node (ref "D48") (pin "2") (pinfunction "A_2") (pintype "unspecified"))
      (node (ref "SW50") (pin "2") (pinfunction "Row_2") (pintype "unspecified"))
    )
    (net (code "69") (name "Net-(D49-A)") (class "Default")
      (node (ref "D49") (pin "2") (pinfunction "A_2") (pintype "unspecified"))
      (node (ref "SW51") (pin "2") (pinfunction "Row_2") (pintype "unspecified"))
    )
    (net (code "70") (name "Net-(D50-A)") (class "Default")
      (node (ref "D50") (pin "2") (pinfunction "A_2") (pintype "unspecified"))
      (node (ref "SW52") (pin "2") (pinfunction "Row_2") (pintype "unspecified"))
    )
    (net (code "71") (name "Net-(D51-A)") (class "Default")
      (node (ref "D51") (pin "2") (pinfunction "A_2") (pintype "unspecified"))
      (node (ref "SW53") (pin "2") (pinfunction "Row_2") (pintype "unspecified"))
    )
    (net (code "72") (name "Net-(D52-A)") (class "Default")
      (node (ref "D52") (pin "2") (pinfunction "A_2") (pintype "unspecified"))
      (node (ref "SW54") (pin "2") (pinfunction "Row_2") (pintype "unspecified"))
    )
    (net (code "73") (name "Net-(D53-A)") (class "Default")
      (node (ref "D53") (pin "2") (pinfunction "A_2") (pintype "unspecified"))
      (node (ref "SW55") (pin "2") (pinfunction "Row_2") (pintype "unspecified"))
    )
    (net (code "74") (name "Net-(D54-A)") (class "Default")
      (node (ref "D54") (pin "2") (pinfunction "A_2") (pintype "unspecified"))
      (node (ref "SW56") (pin "2") (pinfunction "Row_2") (pintype "unspecified"))
    )
    (net (code "75") (name "Net-(D55-A)") (class "Default")
      (node (ref "D55") (pin "2") (pinfunction "A_2") (pintype "unspecified"))
      (node (ref "SW57") (pin "2") (pinfunction "Row_2") (pintype "unspecified"))
    )
    (net (code "76") (name "Net-(D56-A)") (class "Default")
      (node (ref "D56") (pin "2") (pinfunction "A_2") (pintype "unspecified"))
      (node (ref "SW58") (pin "2") (pinfunction "Row_2") (pintype "unspecified"))
    )
    (net (code "77") (name "Net-(D57-A)") (class "Default")
      (node (ref "D57") (pin "2") (pinfunction "A_2") (pintype "unspecified"))
      (node (ref "SW59") (pin "2") (pinfunction "Row_2") (pintype "unspecified"))
    )
    (net (code "78") (name "Net-(D58-A)") (class "Default")
      (node (ref "D58") (pin "2") (pinfunction "A_2") (pintype "unspecified"))
      (node (ref "SW60") (pin "2") (pinfunction "Row_2") (pintype "unspecified"))
    )
    (net (code "79") (name "Net-(D59-A)") (class "Default")
      (node (ref "D59") (pin "2") (pinfunction "A_2") (pintype "unspecified"))
      (node (ref "SW61") (pin "2") (pinfunction "Row_2") (pintype "unspecified"))
    )
    (net (code "80") (name "Net-(D60-A)") (class "Default")
      (node (ref "D60") (pin "2") (pinfunction "A_2") (pintype "unspecified"))
      (node (ref "SW62") (pin "2") (pinfunction "Row_2") (pintype "unspecified"))
    )
    (net (code "81") (name "Net-(D61-A)") (class "Default")
      (node (ref "D61") (pin "2") (pinfunction "A_2") (pintype "unspecified"))
      (node (ref "SW63") (pin "2") (pinfunction "Row_2") (pintype "unspecified"))
    )
    (net (code "82") (name "Net-(D62-A)") (class "Default")
      (node (ref "D62") (pin "2") (pinfunction "A_2") (pintype "unspecified"))
      (node (ref "SW64") (pin "2") (pinfunction "Row_2") (pintype "unspecified"))
    )
    (net (code "83") (name "Net-(D63-A)") (class "Default")
      (node (ref "D63") (pin "2") (pinfunction "A_2") (pintype "unspecified"))
      (node (ref "SW65") (pin "2") (pinfunction "Row_2") (pintype "unspecified"))
    )
    (net (code "84") (name "Net-(D64-A)") (class "Default")
      (node (ref "D64") (pin "2") (pinfunction "A_2") (pintype "unspecified"))
      (node (ref "SW66") (pin "2") (pinfunction "Row_2") (pintype "unspecified"))
    )
    (net (code "85") (name "Net-(D65-A)") (class "Default")
      (node (ref "D65") (pin "2") (pinfunction "A_2") (pintype "unspecified"))
      (node (ref "SW67") (pin "2") (pinfunction "Row_2") (pintype "unspecified"))
    )
    (net (code "86") (name "Net-(D66-A)") (class "Default")
      (node (ref "D66") (pin "2") (pinfunction "A_2") (pintype "unspecified"))
      (node (ref "ENC1") (pin "D") (pinfunction "D_D") (pintype "unspecified"))
    )
    (net (code "87") (name "Net-(D67-A)") (class "Default")
      (node (ref "D67") (pin "2") (pinfunction "A_2") (pintype "unspecified"))
      (node (ref "SW68") (pin "2") (pinfunction "Row_2") (pintype "unspecified"))
    )
    (net (code "88") (name "Net-(D68-A)") (class "Default")
      (node (ref "D68") (pin "2") (pinfunction "A_2") (pintype "unspecified"))
      (node (ref "SW69") (pin "2") (pinfunction "Row_2") (pintype "unspecified"))
    )
    (net (code "89") (name "Net-(D69-A)") (class "Default")
      (node (ref "D69") (pin "2") (pinfunction "A_2") (pintype "unspecified"))
      (node (ref "SW70") (pin "2") (pinfunction "Row_2") (pintype "unspecified"))
    )
    (net (code "90") (name "Net-(D70-A)") (class "Default")
      (node (ref "D70") (pin "2") (pinfunction "A_2") (pintype "unspecified"))
      (node (ref "SW71") (pin "2") (pinfunction "Row_2") (pintype "unspecified"))
    )
    (net (code "91") (name "Net-(PWR-K)") (class "Default")
      (node (ref "PWR") (pin "2") (pinfunction "K_2") (pintype "unspecified"))
      (node (ref "R73") (pin "2") (pinfunction "2_2") (pintype "unspecified"))
    )
    (net (code "92") (name "Net-(SW1-GND-LED)") (class "Default")
      (node (ref "R1") (pin "2") (pinfunction "2_2") (pintype "unspecified"))
      (node (ref "SW1") (pin "4") (pinfunction "GND-LED_4") (pintype "unspecified"))
    )
    (net (code "93") (name "Net-(SW2-GND-LED)") (class "Default")
      (node (ref "R2") (pin "2") (pinfunction "2_2") (pintype "unspecified"))
      (node (ref "SW2") (pin "4") (pinfunction "GND-LED_4") (pintype "unspecified"))
    )
    (net (code "94") (name "Net-(SW3-GND-LED)") (class "Default")
      (node (ref "R3") (pin "2") (pinfunction "2_2") (pintype "unspecified"))
      (node (ref "SW3") (pin "4") (pinfunction "GND-LED_4") (pintype "unspecified"))
    )
    (net (code "95") (name "Net-(SW4-GND-LED)") (class "Default")
      (node (ref "R4") (pin "2") (pinfunction "2_2") (pintype "unspecified"))
      (node (ref "SW4") (pin "4") (pinfunction "GND-LED_4") (pintype "unspecified"))
    )
    (net (code "96") (name "Net-(SW5-GND-LED)") (class "Default")
      (node (ref "R5") (pin "2") (pinfunction "2_2") (pintype "unspecified"))
      (node (ref "SW5") (pin "4") (pinfunction "GND-LED_4") (pintype "unspecified"))
    )
    (net (code "97") (name "Net-(SW6-GND-LED)") (class "Default")
      (node (ref "R6") (pin "2") (pinfunction "2_2") (pintype "unspecified"))
      (node (ref "SW6") (pin "4") (pinfunction "GND-LED_4") (pintype "unspecified"))
    )
    (net (code "98") (name "Net-(SW7-GND-LED)") (class "Default")
      (node (ref "R7") (pin "2") (pinfunction "2_2") (pintype "unspecified"))
      (node (ref "SW7") (pin "4") (pinfunction "GND-LED_4") (pintype "unspecified"))
    )
    (net (code "99") (name "Net-(SW8-GND-LED)") (class "Default")
      (node (ref "R8") (pin "2") (pinfunction "2_2") (pintype "unspecified"))
      (node (ref "SW8") (pin "4") (pinfunction "GND-LED_4") (pintype "unspecified"))
    )
    (net (code "100") (name "Net-(SW9-GND-LED)") (class "Default")
      (node (ref "R9") (pin "2") (pinfunction "2_2") (pintype "unspecified"))
      (node (ref "SW9") (pin "4") (pinfunction "GND-LED_4") (pintype "unspecified"))
    )
    (net (code "101") (name "Net-(SW10-GND-LED)") (class "Default")
      (node (ref "R10") (pin "2") (pinfunction "2_2") (pintype "unspecified"))
      (node (ref "SW10") (pin "4") (pinfunction "GND-LED_4") (pintype "unspecified"))
    )
    (net (code "102") (name "Net-(SW11-GND-LED)") (class "Default")
      (node (ref "R11") (pin "2") (pinfunction "2_2") (pintype "unspecified"))
      (node (ref "SW11") (pin "4") (pinfunction "GND-LED_4") (pintype "unspecified"))
    )
    (net (code "103") (name "Net-(SW12-GND-LED)") (class "Default")
      (node (ref "R12") (pin "2") (pinfunction "2_2") (pintype "unspecified"))
      (node (ref "SW12") (pin "4") (pinfunction "GND-LED_4") (pintype "unspecified"))
    )
    (net (code "104") (name "Net-(SW13-GND-LED)") (class "Default")
      (node (ref "R13") (pin "2") (pinfunction "2_2") (pintype "unspecified"))
      (node (ref "SW13") (pin "4") (pinfunction "GND-LED_4") (pintype "unspecified"))
    )
    (net (code "105") (name "Net-(SW14-GND-LED)") (class "Default")
      (node (ref "R14") (pin "2") (pinfunction "2_2") (pintype "unspecified"))
      (node (ref "SW14") (pin "4") (pinfunction "GND-LED_4") (pintype "unspecified"))
    )
    (net (code "106") (name "Net-(SW15-GND-LED)") (class "Default")
      (node (ref "R15") (pin "2") (pinfunction "2_2") (pintype "unspecified"))
      (node (ref "SW15") (pin "4") (pinfunction "GND-LED_4") (pintype "unspecified"))
    )
    (net (code "107") (name "Net-(SW16-GND-LED)") (class "Default")
      (node (ref "R16") (pin "2") (pinfunction "2_2") (pintype "unspecified"))
      (node (ref "SW16") (pin "4") (pinfunction "GND-LED_4") (pintype "unspecified"))
    )
    (net (code "108") (name "Net-(SW17-GND-LED)") (class "Default")
      (node (ref "R17") (pin "2") (pinfunction "2_2") (pintype "unspecified"))
      (node (ref "SW17") (pin "4") (pinfunction "GND-LED_4") (pintype "unspecified"))
    )
    (net (code "109") (name "Net-(SW18-GND-LED)") (class "Default")
      (node (ref "R18") (pin "2") (pinfunction "2_2") (pintype "unspecified"))
      (node (ref "SW18") (pin "4") (pinfunction "GND-LED_4") (pintype "unspecified"))
    )
    (net (code "110") (name "Net-(SW19-GND-LED)") (class "Default")
      (node (ref "R19") (pin "2") (pinfunction "2_2") (pintype "unspecified"))
      (node (ref "SW19") (pin "4") (pinfunction "GND-LED_4") (pintype "unspecified"))
    )
    (net (code "111") (name "Net-(SW20-GND-LED)") (class "Default")
      (node (ref "R20") (pin "2") (pinfunction "2_2") (pintype "unspecified"))
      (node (ref "SW20") (pin "4") (pinfunction "GND-LED_4") (pintype "unspecified"))
    )
    (net (code "112") (name "Net-(SW21-GND-LED)") (class "Default")
      (node (ref "R21") (pin "2") (pinfunction "2_2") (pintype "unspecified"))
      (node (ref "SW21") (pin "4") (pinfunction "GND-LED_4") (pintype "unspecified"))
    )
    (net (code "113") (name "Net-(SW22-GND-LED)") (class "Default")
      (node (ref "R22") (pin "2") (pinfunction "2_2") (pintype "unspecified"))
      (node (ref "SW22") (pin "4") (pinfunction "GND-LED_4") (pintype "unspecified"))
    )
    (net (code "114") (name "Net-(SW23-GND-LED)") (class "Default")
      (node (ref "R23") (pin "2") (pinfunction "2_2") (pintype "unspecified"))
      (node (ref "SW23") (pin "4") (pinfunction "GND-LED_4") (pintype "unspecified"))
    )
    (net (code "115") (name "Net-(SW24-GND-LED)") (class "Default")
      (node (ref "R24") (pin "2") (pinfunction "2_2") (pintype "unspecified"))
      (node (ref "SW24") (pin "4") (pinfunction "GND-LED_4") (pintype "unspecified"))
    )
    (net (code "116") (name "Net-(SW25-GND-LED)") (class "Default")
      (node (ref "R25") (pin "2") (pinfunction "2_2") (pintype "unspecified"))
      (node (ref "SW25") (pin "4") (pinfunction "GND-LED_4") (pintype "unspecified"))
    )
    (net (code "117") (name "Net-(SW26-GND-LED)") (class "Default")
      (node (ref "R26") (pin "2") (pinfunction "2_2") (pintype "unspecified"))
      (node (ref "SW26") (pin "4") (pinfunction "GND-LED_4") (pintype "unspecified"))
    )
    (net (code "118") (name "Net-(SW27-GND-LED)") (class "Default")
      (node (ref "R27") (pin "2") (pinfunction "2_2") (pintype "unspecified"))
      (node (ref "SW27") (pin "4") (pinfunction "GND-LED_4") (pintype "unspecified"))
    )
    (net (code "119") (name "Net-(SW28-GND-LED)") (class "Default")
      (node (ref "R28") (pin "2") (pinfunction "2_2") (pintype "unspecified"))
      (node (ref "SW28") (pin "4") (pinfunction "GND-LED_4") (pintype "unspecified"))
    )
    (net (code "120") (name "Net-(SW29-GND-LED)") (class "Default")
      (node (ref "R29") (pin "2") (pinfunction "2_2") (pintype "unspecified"))
      (node (ref "SW29") (pin "4") (pinfunction "GND-LED_4") (pintype "unspecified"))
    )
    (net (code "121") (name "Net-(SW30-GND-LED)") (class "Default")
      (node (ref "R30") (pin "2") (pinfunction "2_2") (pintype "unspecified"))
      (node (ref "SW30") (pin "4") (pinfunction "GND-LED_4") (pintype "unspecified"))
    )
    (net (code "122") (name "Net-(SW31-GND-LED)") (class "Default")
      (node (ref "R31") (pin "2") (pinfunction "2_2") (pintype "unspecified"))
      (node (ref "SW31") (pin "4") (pinfunction "GND-LED_4") (pintype "unspecified"))
      (node (ref "SW32") (pin "4") (pinfunction "GND-LED_4") (pintype "unspecified"))
    )
    (net (code "123") (name "Net-(SW33-GND-LED)") (class "Default")
      (node (ref "R32") (pin "2") (pinfunction "2_2") (pintype "unspecified"))
      (node (ref "SW33") (pin "4") (pinfunction "GND-LED_4") (pintype "unspecified"))
    )
    (net (code "124") (name "Net-(SW34-GND-LED)") (class "Default")
      (node (ref "R33") (pin "2") (pinfunction "2_2") (pintype "unspecified"))
      (node (ref "SW34") (pin "4") (pinfunction "GND-LED_4") (pintype "unspecified"))
    )
    (net (code "125") (name "Net-(SW35-GND-LED)") (class "Default")
      (node (ref "R34") (pin "2") (pinfunction "2_2") (pintype "unspecified"))
      (node (ref "SW35") (pin "4") (pinfunction "GND-LED_4") (pintype "unspecified"))
    )
    (net (code "126") (name "Net-(SW36-GND-LED)") (class "Default")
      (node (ref "R35") (pin "2") (pinfunction "2_2") (pintype "unspecified"))
      (node (ref "SW36") (pin "4") (pinfunction "GND-LED_4") (pintype "unspecified"))
      (node (ref "SW37") (pin "4") (pinfunction "GND-LED_4") (pintype "unspecified"))
    )
    (net (code "127") (name "Net-(SW38-GND-LED)") (class "Default")
      (node (ref "R36") (pin "2") (pinfunction "2_2") (pintype "unspecified"))
      (node (ref "SW38") (pin "4") (pinfunction "GND-LED_4") (pintype "unspecified"))
    )
    (net (code "128") (name "Net-(SW39-GND-LED)") (class "Default")
      (node (ref "R37") (pin "2") (pinfunction "2_2") (pintype "unspecified"))
      (node (ref "SW39") (pin "4") (pinfunction "GND-LED_4") (pintype "unspecified"))
    )
    (net (code "129") (name "Net-(SW40-GND-LED)") (class "Default")
      (node (ref "R38") (pin "2") (pinfunction "2_2") (pintype "unspecified"))
      (node (ref "SW40") (pin "4") (pinfunction "GND-LED_4") (pintype "unspecified"))
    )
    (net (code "130") (name "Net-(SW41-GND-LED)") (class "Default")
      (node (ref "R39") (pin "2") (pinfunction "2_2") (pintype "unspecified"))
      (node (ref "SW41") (pin "4") (pinfunction "GND-LED_4") (pintype "unspecified"))
    )
    (net (code "131") (name "Net-(SW42-GND-LED)") (class "Default")
      (node (ref "R40") (pin "2") (pinfunction "2_2") (pintype "unspecified"))
      (node (ref "SW42") (pin "4") (pinfunction "GND-LED_4") (pintype "unspecified"))
    )
    (net (code "132") (name "Net-(SW43-GND-LED)") (class "Default")
      (node (ref "R41") (pin "2") (pinfunction "2_2") (pintype "unspecified"))
      (node (ref "SW43") (pin "4") (pinfunction "GND-LED_4") (pintype "unspecified"))
    )
    (net (code "133") (name "Net-(SW44-GND-LED)") (class "Default")
      (node (ref "R42") (pin "2") (pinfunction "2_2") (pintype "unspecified"))
      (node (ref "SW44") (pin "4") (pinfunction "GND-LED_4") (pintype "unspecified"))
    )
    (net (code "134") (name "Net-(SW45-GND-LED)") (class "Default")
      (node (ref "R43") (pin "2") (pinfunction "2_2") (pintype "unspecified"))
      (node (ref "SW45") (pin "4") (pinfunction "GND-LED_4") (pintype "unspecified"))
    )
    (net (code "135") (name "Net-(SW46-GND-LED)") (class "Default")
      (node (ref "R44") (pin "2") (pinfunction "2_2") (pintype "unspecified"))
      (node (ref "SW46") (pin "4") (pinfunction "GND-LED_4") (pintype "unspecified"))
    )
    (net (code "136") (name "Net-(SW47-GND-LED)") (class "Default")
      (node (ref "R45") (pin "2") (pinfunction "2_2") (pintype "unspecified"))
      (node (ref "SW47") (pin "4") (pinfunction "GND-LED_4") (pintype "unspecified"))
    )
    (net (code "137") (name "Net-(SW48-GND-LED)") (class "Default")
      (node (ref "R46") (pin "2") (pinfunction "2_2") (pintype "unspecified"))
      (node (ref "SW48") (pin "4") (pinfunction "GND-LED_4") (pintype "unspecified"))
    )
    (net (code "138") (name "Net-(SW49-GND-LED)") (class "Default")
      (node (ref "R47") (pin "2") (pinfunction "2_2") (pintype "unspecified"))
      (node (ref "SW49") (pin "4") (pinfunction "GND-LED_4") (pintype "unspecified"))
    )
    (net (code "139") (name "Net-(SW50-GND-LED)") (class "Default")
      (node (ref "R48") (pin "2") (pinfunction "2_2") (pintype "unspecified"))
      (node (ref "SW50") (pin "4") (pinfunction "GND-LED_4") (pintype "unspecified"))
    )
    (net (code "140") (name "Net-(SW51-GND-LED)") (class "Default")
      (node (ref "R49") (pin "2") (pinfunction "2_2") (pintype "unspecified"))
      (node (ref "SW51") (pin "4") (pinfunction "GND-LED_4") (pintype "unspecified"))
    )
    (net (code "141") (name "Net-(SW52-GND-LED)") (class "Default")
      (node (ref "R50") (pin "2") (pinfunction "2_2") (pintype "unspecified"))
      (node (ref "SW52") (pin "4") (pinfunction "GND-LED_4") (pintype "unspecified"))
    )
    (net (code "142") (name "Net-(SW53-GND-LED)") (class "Default")
      (node (ref "R51") (pin "2") (pinfunction "2_2") (pintype "unspecified"))
      (node (ref "SW53") (pin "4") (pinfunction "GND-LED_4") (pintype "unspecified"))
    )
    (net (code "143") (name "Net-(SW54-GND-LED)") (class "Default")
      (node (ref "R52") (pin "2") (pinfunction "2_2") (pintype "unspecified"))
      (node (ref "SW54") (pin "4") (pinfunction "GND-LED_4") (pintype "unspecified"))
    )
    (net (code "144") (name "Net-(SW55-GND-LED)") (class "Default")
      (node (ref "R53") (pin "2") (pinfunction "2_2") (pintype "unspecified"))
      (node (ref "SW55") (pin "4") (pinfunction "GND-LED_4") (pintype "unspecified"))
    )
    (net (code "145") (name "Net-(SW56-GND-LED)") (class "Default")
      (node (ref "R54") (pin "2") (pinfunction "2_2") (pintype "unspecified"))
      (node (ref "SW56") (pin "4") (pinfunction "GND-LED_4") (pintype "unspecified"))
    )
    (net (code "146") (name "Net-(SW57-GND-LED)") (class "Default")
      (node (ref "R55") (pin "2") (pinfunction "2_2") (pintype "unspecified"))
      (node (ref "SW57") (pin "4") (pinfunction "GND-LED_4") (pintype "unspecified"))
    )
    (net (code "147") (name "Net-(SW58-GND-LED)") (class "Default")
      (node (ref "R56") (pin "2") (pinfunction "2_2") (pintype "unspecified"))
      (node (ref "SW58") (pin "4") (pinfunction "GND-LED_4") (pintype "unspecified"))
    )
    (net (code "148") (name "Net-(SW59-GND-LED)") (class "Default")
      (node (ref "R57") (pin "2") (pinfunction "2_2") (pintype "unspecified"))
      (node (ref "SW59") (pin "4") (pinfunction "GND-LED_4") (pintype "unspecified"))
    )
    (net (code "149") (name "Net-(SW60-GND-LED)") (class "Default")
      (node (ref "R58") (pin "2") (pinfunction "2_2") (pintype "unspecified"))
      (node (ref "SW60") (pin "4") (pinfunction "GND-LED_4") (pintype "unspecified"))
    )
    (net (code "150") (name "Net-(SW61-GND-LED)") (class "Default")
      (node (ref "R59") (pin "2") (pinfunction "2_2") (pintype "unspecified"))
      (node (ref "SW61") (pin "4") (pinfunction "GND-LED_4") (pintype "unspecified"))
    )
    (net (code "151") (name "Net-(SW62-GND-LED)") (class "Default")
      (node (ref "R60") (pin "2") (pinfunction "2_2") (pintype "unspecified"))
      (node (ref "SW62") (pin "4") (pinfunction "GND-LED_4") (pintype "unspecified"))
    )
    (net (code "152") (name "Net-(SW63-GND-LED)") (class "Default")
      (node (ref "R61") (pin "2") (pinfunction "2_2") (pintype "unspecified"))
      (node (ref "SW63") (pin "4") (pinfunction "GND-LED_4") (pintype "unspecified"))
    )
    (net (code "153") (name "Net-(SW64-GND-LED)") (class "Default")
      (node (ref "R62") (pin "2") (pinfunction "2_2") (pintype "unspecified"))
      (node (ref "SW64") (pin "4") (pinfunction "GND-LED_4") (pintype "unspecified"))
    )
    (net (code "154") (name "Net-(SW65-GND-LED)") (class "Default")
      (node (ref "R63") (pin "2") (pinfunction "2_2") (pintype "unspecified"))
      (node (ref "SW65") (pin "4") (pinfunction "GND-LED_4") (pintype "unspecified"))
    )
    (net (code "155") (name "Net-(SW66-GND-LED)") (class "Default")
      (node (ref "R64") (pin "2") (pinfunction "2_2") (pintype "unspecified"))
      (node (ref "SW66") (pin "4") (pinfunction "GND-LED_4") (pintype "unspecified"))
    )
    (net (code "156") (name "Net-(SW67-GND-LED)") (class "Default")
      (node (ref "R65") (pin "2") (pinfunction "2_2") (pintype "unspecified"))
      (node (ref "SW67") (pin "4") (pinfunction "GND-LED_4") (pintype "unspecified"))
    )
    (net (code "157") (name "Net-(SW68-GND-LED)") (class "Default")
      (node (ref "R66") (pin "2") (pinfunction "2_2") (pintype "unspecified"))
      (node (ref "SW68") (pin "4") (pinfunction "GND-LED_4") (pintype "unspecified"))
    )
    (net (code "158") (name "Net-(SW69-GND-LED)") (class "Default")
      (node (ref "R67") (pin "2") (pinfunction "2_2") (pintype "unspecified"))
      (node (ref "SW69") (pin "4") (pinfunction "GND-LED_4") (pintype "unspecified"))
    )
    (net (code "159") (name "Net-(SW70-GND-LED)") (class "Default")
      (node (ref "R68") (pin "2") (pinfunction "2_2") (pintype "unspecified"))
      (node (ref "SW70") (pin "4") (pinfunction "GND-LED_4") (pintype "unspecified"))
    )
    (net (code "160") (name "Net-(SW71-GND-LED)") (class "Default")
      (node (ref "R69") (pin "2") (pinfunction "2_2") (pintype "unspecified"))
      (node (ref "SW71") (pin "4") (pinfunction "GND-LED_4") (pintype "unspecified"))
    )
    (net (code "161") (name "Net-(U1-AREF)") (class "Default")
      (node (ref "C9") (pin "1") (pinfunction "1_1") (pintype "unspecified"))
      (node (ref "U1") (pin "42") (pinfunction "AREF_42") (pintype "unspecified"))
    )
    (net (code "162") (name "Net-(U1-D+)") (class "Default")
      (node (ref "R71") (pin "1") (pinfunction "1_1") (pintype "input"))
      (node (ref "U1") (pin "4") (pinfunction "D+_4") (pintype "unspecified"))
    )
    (net (code "163") (name "Net-(U1-D-)") (class "Default")
      (node (ref "R70") (pin "1") (pinfunction "1_1") (pintype "input"))
      (node (ref "U1") (pin "3") (pinfunction "D-_3") (pintype "unspecified"))
    )
    (net (code "164") (name "Net-(U1-PE2(HWB#))") (class "Default")
      (node (ref "R72") (pin "2") (pinfunction "2_2") (pintype "input"))
      (node (ref "U1") (pin "33") (pinfunction "PE2(HWB#)_33") (pintype "unspecified"))
    )
    (net (code "165") (name "Net-(U1-UCap)") (class "Default")
      (node (ref "C12") (pin "2") (pinfunction "2_2") (pintype "input"))
      (node (ref "U1") (pin "6") (pinfunction "UCap_6") (pintype "unspecified"))
    )
    (net (code "166") (name "Net-(U1-XTAL1)") (class "Default")
      (node (ref "C11") (pin "2") (pinfunction "2_2") (pintype "input"))
      (node (ref "U1") (pin "17") (pinfunction "XTAL1_17") (pintype "unspecified"))
      (node (ref "X1") (pin "1") (pinfunction "OSC1_1") (pintype "unspecified"))
    )
    (net (code "167") (name "Net-(U1-XTAL2)") (class "Default")
      (node (ref "C10") (pin "2") (pinfunction "2_2") (pintype "input"))
      (node (ref "U1") (pin "16") (pinfunction "XTAL2_16") (pintype "unspecified"))
      (node (ref "X1") (pin "3") (pinfunction "OSC2_3") (pintype "unspecified"))
    )
    (net (code "168") (name "Net-(USBC1-CC1)") (class "Default")
      (node (ref "R74") (pin "1") (pinfunction "1_1") (pintype "unspecified"))
      (node (ref "USBC1") (pin "A5") (pinfunction "CC1_A5") (pintype "unspecified"))
    )
    (net (code "169") (name "Net-(USBC1-CC2)") (class "Default")
      (node (ref "R75") (pin "2") (pinfunction "2_2") (pintype "unspecified"))
      (node (ref "USBC1") (pin "B5") (pinfunction "CC2_B5") (pintype "unspecified"))
    )
    (net (code "170") (name "Reset") (class "Default")
      (node (ref "BUTTON") (pin "1") (pinfunction "A_1") (pintype "unspecified"))
      (node (ref "BUTTON") (pin "2") (pinfunction "B_2") (pintype "unspecified"))
      (node (ref "R76") (pin "2") (pinfunction "2_2") (pintype "input"))
      (node (ref "U1") (pin "13") (pinfunction "RESET#_13") (pintype "unspecified"))
    )
    (net (code "171") (name "Row0") (class "Default")
      (node (ref "D1") (pin "1") (pinfunction "K_1") (pintype "unspecified"))
      (node (ref "D11") (pin "1") (pinfunction "K_1") (pintype "unspecified"))
      (node (ref "D16") (pin "1") (pinfunction "K_1") (pintype "unspecified"))
      (node (ref "D21") (pin "1") (pinfunction "K_1") (pintype "unspecified"))
      (node (ref "D26") (pin "1") (pinfunction "K_1") (pintype "unspecified"))
      (node (ref "D31") (pin "1") (pinfunction "K_1") (pintype "unspecified"))
      (node (ref "D36") (pin "1") (pinfunction "K_1") (pintype "unspecified"))
      (node (ref "D41") (pin "1") (pinfunction "K_1") (pintype "unspecified"))
      (node (ref "D46") (pin "1") (pinfunction "K_1") (pintype "unspecified"))
      (node (ref "D51") (pin "1") (pinfunction "K_1") (pintype "unspecified"))
      (node (ref "D56") (pin "1") (pinfunction "K_1") (pintype "unspecified"))
      (node (ref "D6") (pin "1") (pinfunction "K_1") (pintype "unspecified"))
      (node (ref "D61") (pin "1") (pinfunction "K_1") (pintype "unspecified"))
      (node (ref "D66") (pin "1") (pinfunction "K_1") (pintype "unspecified"))
      (node (ref "U1") (pin "8") (pinfunction "PB0(SS/PCINT0)_8") (pintype "unspecified"))
    )
    (net (code "172") (name "Row1") (class "Default")
      (node (ref "D12") (pin "1") (pinfunction "K_1") (pintype "unspecified"))
      (node (ref "D17") (pin "1") (pinfunction "K_1") (pintype "unspecified"))
      (node (ref "D2") (pin "1") (pinfunction "K_1") (pintype "unspecified"))
      (node (ref "D22") (pin "1") (pinfunction "K_1") (pintype "unspecified"))
      (node (ref "D27") (pin "1") (pinfunction "K_1") (pintype "unspecified"))
      (node (ref "D32") (pin "1") (pinfunction "K_1") (pintype "unspecified"))
      (node (ref "D37") (pin "1") (pinfunction "K_1") (pintype "unspecified"))
      (node (ref "D42") (pin "1") (pinfunction "K_1") (pintype "unspecified"))
      (node (ref "D47") (pin "1") (pinfunction "K_1") (pintype "unspecified"))
      (node (ref "D52") (pin "1") (pinfunction "K_1") (pintype "unspecified"))
      (node (ref "D57") (pin "1") (pinfunction "K_1") (pintype "unspecified"))
      (node (ref "D62") (pin "1") (pinfunction "K_1") (pintype "unspecified"))
      (node (ref "D67") (pin "1") (pinfunction "K_1") (pintype "unspecified"))
      (node (ref "D7") (pin "1") (pinfunction "K_1") (pintype "unspecified"))
      (node (ref "U1") (pin "9") (pinfunction "PB1(PCINT1/SCLK)_9") (pintype "unspecified"))
    )
    (net (code "173") (name "Row2") (class "Default")
      (node (ref "D13") (pin "1") (pinfunction "K_1") (pintype "unspecified"))
      (node (ref "D18") (pin "1") (pinfunction "K_1") (pintype "unspecified"))
      (node (ref "D23") (pin "1") (pinfunction "K_1") (pintype "unspecified"))
      (node (ref "D28") (pin "1") (pinfunction "K_1") (pintype "unspecified"))
      (node (ref "D3") (pin "1") (pinfunction "K_1") (pintype "unspecified"))
      (node (ref "D33") (pin "1") (pinfunction "K_1") (pintype "unspecified"))
      (node (ref "D38") (pin "1") (pinfunction "K_1") (pintype "unspecified"))
      (node (ref "D43") (pin "1") (pinfunction "K_1") (pintype "unspecified"))
      (node (ref "D48") (pin "1") (pinfunction "K_1") (pintype "unspecified"))
      (node (ref "D53") (pin "1") (pinfunction "K_1") (pintype "unspecified"))
      (node (ref "D58") (pin "1") (pinfunction "K_1") (pintype "unspecified"))
      (node (ref "D63") (pin "1") (pinfunction "K_1") (pintype "unspecified"))
      (node (ref "D68") (pin "1") (pinfunction "K_1") (pintype "unspecified"))
      (node (ref "D8") (pin "1") (pinfunction "K_1") (pintype "unspecified"))
      (node (ref "U1") (pin "10") (pinfunction "PB2(PDI/PCINT2/MOSI)_10") (pintype "unspecified"))
    )
    (net (code "174") (name "Row3") (class "Default")
      (node (ref "D14") (pin "1") (pinfunction "K_1") (pintype "unspecified"))
      (node (ref "D19") (pin "1") (pinfunction "K_1") (pintype "unspecified"))
      (node (ref "D24") (pin "1") (pinfunction "K_1") (pintype "unspecified"))
      (node (ref "D29") (pin "1") (pinfunction "K_1") (pintype "unspecified"))
      (node (ref "D34") (pin "1") (pinfunction "K_1") (pintype "unspecified"))
      (node (ref "D39") (pin "1") (pinfunction "K_1") (pintype "unspecified"))
      (node (ref "D4") (pin "1") (pinfunction "K_1") (pintype "unspecified"))
      (node (ref "D44") (pin "1") (pinfunction "K_1") (pintype "unspecified"))
      (node (ref "D49") (pin "1") (pinfunction "K_1") (pintype "unspecified"))
      (node (ref "D54") (pin "1") (pinfunction "K_1") (pintype "unspecified"))
      (node (ref "D59") (pin "1") (pinfunction "K_1") (pintype "unspecified"))
      (node (ref "D64") (pin "1") (pinfunction "K_1") (pintype "unspecified"))
      (node (ref "D69") (pin "1") (pinfunction "K_1") (pintype "unspecified"))
      (node (ref "D9") (pin "1") (pinfunction "K_1") (pintype "unspecified"))
      (node (ref "U1") (pin "11") (pinfunction "PB3(PDO/PCINT3/MISO)_11") (pintype "unspecified"))
    )
    (net (code "175") (name "Row4") (class "Default")
      (node (ref "D10") (pin "1") (pinfunction "K_1") (pintype "unspecified"))
      (node (ref "D15") (pin "1") (pinfunction "K_1") (pintype "unspecified"))
      (node (ref "D20") (pin "1") (pinfunction "K_1") (pintype "unspecified"))
      (node (ref "D25") (pin "1") (pinfunction "K_1") (pintype "unspecified"))
      (node (ref "D30") (pin "1") (pinfunction "K_1") (pintype "unspecified"))
      (node (ref "D35") (pin "1") (pinfunction "K_1") (pintype "unspecified"))
      (node (ref "D40") (pin "1") (pinfunction "K_1") (pintype "unspecified"))
      (node (ref "D45") (pin "1") (pinfunction "K_1") (pintype "unspecified"))
      (node (ref "D5") (pin "1") (pinfunction "K_1") (pintype "unspecified"))
      (node (ref "D50") (pin "1") (pinfunction "K_1") (pintype "unspecified"))
      (node (ref "D55") (pin "1") (pinfunction "K_1") (pintype "unspecified"))
      (node (ref "D60") (pin "1") (pinfunction "K_1") (pintype "unspecified"))
      (node (ref "D65") (pin "1") (pinfunction "K_1") (pintype "unspecified"))
      (node (ref "D70") (pin "1") (pinfunction "K_1") (pintype "unspecified"))
      (node (ref "U1") (pin "12") (pinfunction "PB7(PCINT7/OC0A/OC1C/RTS#)_12") (pintype "unspecified"))
    )
    (net (code "176") (name "SCL") (class "Default")
      (node (ref "OLED1") (pin "2") (pinfunction "SCL_2") (pintype "unspecified"))
      (node (ref "U1") (pin "18") (pinfunction "PD0(OC0B/SCL/INT0)_18") (pintype "unspecified"))
      (node (ref "U2") (pin "2") (pinfunction "._2") (pintype "unspecified"))
    )
    (net (code "177") (name "SDA") (class "Default")
      (node (ref "OLED1") (pin "1") (pinfunction "SDA_1") (pintype "unspecified"))
      (node (ref "U1") (pin "19") (pinfunction "PD1(SDA/INT1)_19") (pintype "unspecified"))
      (node (ref "U2") (pin "1") (pinfunction "._1") (pintype "unspecified"))
    )
    (net (code "178") (name "VCC") (class "Default")
      (node (ref "C3") (pin "2") (pinfunction "2_2") (pintype "unspecified"))
      (node (ref "C4") (pin "2") (pinfunction "2_2") (pintype "unspecified"))
      (node (ref "C5") (pin "2") (pinfunction "2_2") (pintype "unspecified"))
      (node (ref "C6") (pin "2") (pinfunction "2_2") (pintype "unspecified"))
      (node (ref "C7") (pin "2") (pinfunction "2_2") (pintype "input"))
      (node (ref "C8") (pin "2") (pinfunction "2_2") (pintype "unspecified"))
      (node (ref "DIP") (pin "4") (pinfunction "B1_4") (pintype "input"))
      (node (ref "ESD1") (pin "5") (pinfunction "VBUS_5") (pintype "unspecified"))
      (node (ref "OLED1") (pin "3") (pinfunction "Vcc_3") (pintype "unspecified"))
      (node (ref "PWR") (pin "1") (pinfunction "A_1") (pintype "unspecified"))
      (node (ref "R76") (pin "1") (pinfunction "1_1") (pintype "input"))
      (node (ref "U1") (pin "14") (pinfunction "VCC_14") (pintype "unspecified"))
      (node (ref "U1") (pin "2") (pinfunction "UVcc_2") (pintype "unspecified"))
      (node (ref "U1") (pin "24") (pinfunction "AVCC_24") (pintype "unspecified"))
      (node (ref "U1") (pin "34") (pinfunction "VCC_34") (pintype "unspecified"))
      (node (ref "U1") (pin "44") (pinfunction "AVCC_44") (pintype "unspecified"))
      (node (ref "U1") (pin "7") (pinfunction "VBus_7") (pintype "unspecified"))
      (node (ref "U2") (pin "3") (pinfunction "._3") (pintype "unspecified"))
      (node (ref "USBC1") (pin "A4") (pinfunction "VBUS_A4") (pintype "unspecified"))
      (node (ref "USBC1") (pin "A9") (pinfunction "VBUS_A9") (pintype "unspecified"))
    )
    (net (code "179") (name "en1_A") (class "Default")
      (node (ref "C2") (pin "2") (pinfunction "2_2") (pintype "unspecified"))
      (node (ref "ENC1") (pin "A") (pinfunction "A_A") (pintype "unspecified"))
      (node (ref "U1") (pin "25") (pinfunction "PD4(ICP1/ADC8)_25") (pintype "unspecified"))
    )
    (net (code "180") (name "en1_B") (class "Default")
      (node (ref "C1") (pin "1") (pinfunction "1_1") (pintype "unspecified"))
      (node (ref "ENC1") (pin "B") (pinfunction "B_B") (pintype "unspecified"))
      (node (ref "U1") (pin "26") (pinfunction "PD6(T1/OC4D#/ADC9)_26") (pintype "unspecified"))
    )
    (net (code "181") (name "gpio1") (class "Default")
      (node (ref "DIP") (pin "3") (pinfunction "B2_3") (pintype "input"))
      (node (ref "U1") (pin "41") (pinfunction "PF0(ADC0)_41") (pintype "unspecified"))
    )
    (net (code "182") (name "unconnected-(ENC1-Pad6)") (class "Default")
      (node (ref "ENC1") (pin "6") (pinfunction "6_6") (pintype "unspecified+no_connect"))
    )
    (net (code "183") (name "unconnected-(ENC1-Pad7)") (class "Default")
      (node (ref "ENC1") (pin "7") (pinfunction "7_7") (pintype "unspecified+no_connect"))
    )
    (net (code "184") (name "unconnected-(U1-PE6(INT.6{slash}AIN0)-Pad1)") (class "Default")
      (node (ref "U1") (pin "1") (pinfunction "PE6(INT.6/AIN0)_1") (pintype "unspecified+no_connect"))
    )
    (net (code "185") (name "unconnected-(USBC1-Pad0)") (class "Default")
      (node (ref "USBC1") (pin "0") (pinfunction "0_0") (pintype "unspecified+no_connect"))
    )
    (net (code "186") (name "unconnected-(USBC1-Pad0)_1") (class "Default")
      (node (ref "USBC1") (pin "0") (pinfunction "0_0") (pintype "unspecified+no_connect"))
    )
    (net (code "187") (name "unconnected-(USBC1-Pad0)_2") (class "Default")
      (node (ref "USBC1") (pin "0") (pinfunction "0_0") (pintype "unspecified+no_connect"))
    )
    (net (code "188") (name "unconnected-(USBC1-Pad0)_3") (class "Default")
      (node (ref "USBC1") (pin "0") (pinfunction "0_0") (pintype "unspecified+no_connect"))
    )
    (net (code "189") (name "unconnected-(USBC1-SBU1-PadA8)") (class "Default")
      (node (ref "USBC1") (pin "A8") (pinfunction "SBU1_A8") (pintype "unspecified+no_connect"))
    )
    (net (code "190") (name "unconnected-(USBC1-SBU2-PadB8)") (class "Default")
      (node (ref "USBC1") (pin "B8") (pinfunction "SBU2_B8") (pintype "unspecified+no_connect"))
    )
  )
)
